# uc2950-v1.net
KiCad netlist of a schematic drawn in EAGLE
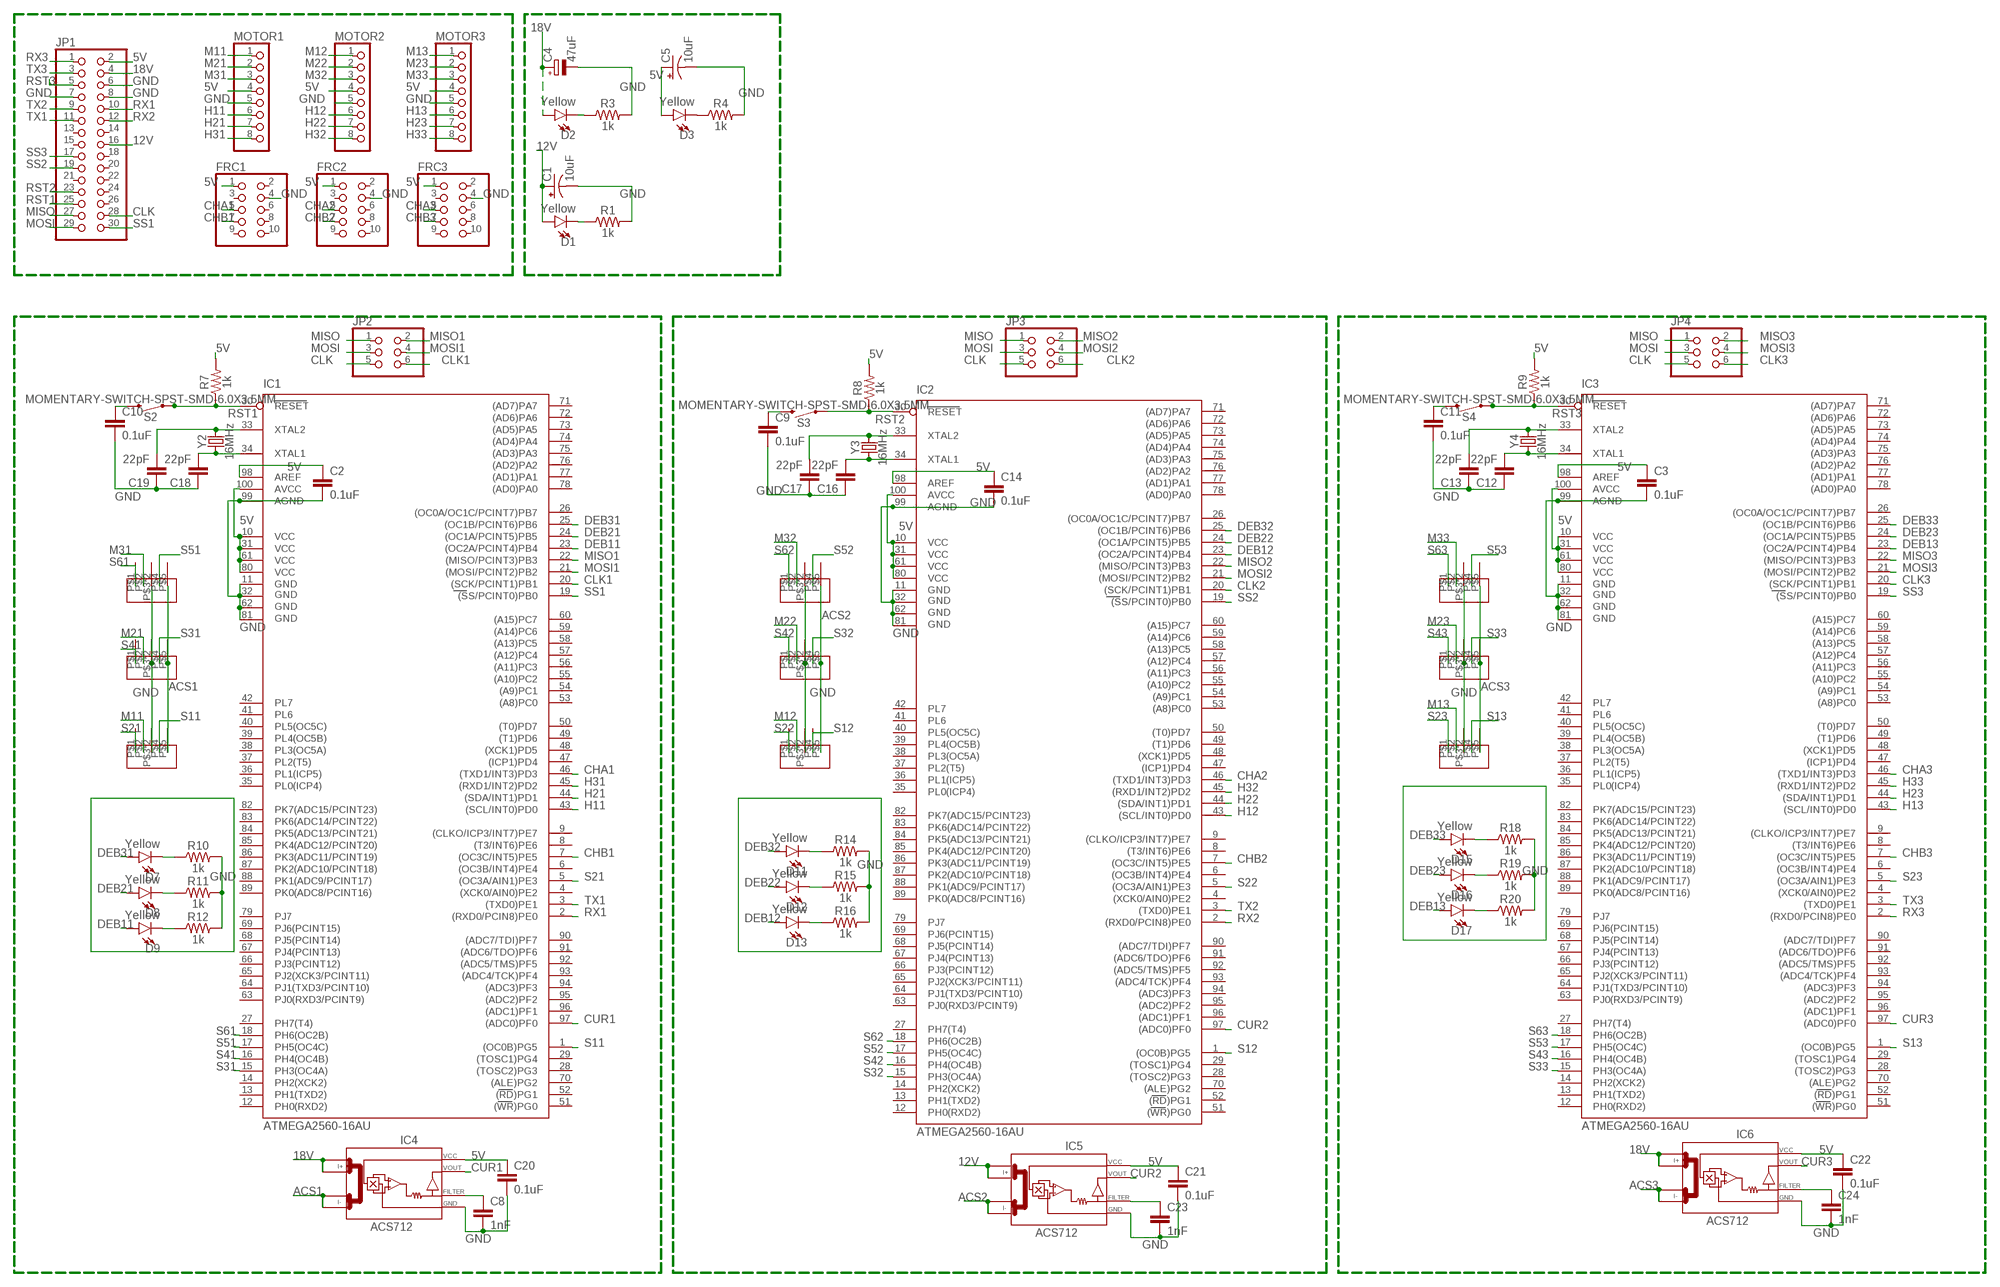
[diagram p0: schematic, sheet 1]

(export (version "E")
  (design (tool "Eeschema 10.0.6"))
  (components
    (comp (ref "C1")
      (value "10uF")
      (footprint "eagle-import:0603-POLAR")
      (libsource (lib "eagle-import") (part "10UF-POLAR-0603-6.3V-20%(TANT)"))
    )
    (comp (ref "C2")
      (value "0.1uF")
      (footprint "eagle-import:0603")
      (libsource (lib "eagle-import") (part "0.1UF-0603-25V-5%"))
    )
    (comp (ref "C3")
      (value "0.1uF")
      (footprint "eagle-import:0603")
      (libsource (lib "eagle-import") (part "0.1UF-0603-25V-5%"))
    )
    (comp (ref "C4")
      (value "47uF")
      (footprint "eagle-import:TAP5-60")
      (libsource (lib "eagle-import") (part "CPOL-EUTAP5-60"))
    )
    (comp (ref "C5")
      (value "10uF")
      (footprint "eagle-import:0603-POLAR")
      (libsource (lib "eagle-import") (part "10UF-POLAR-0603-6.3V-20%(TANT)"))
    )
    (comp (ref "C8")
      (value "1nF")
      (footprint "eagle-import:0603")
      (libsource (lib "eagle-import") (part "1.0NF/1000PF-0603-50V-10%"))
    )
    (comp (ref "C9")
      (value "0.1uF")
      (footprint "eagle-import:0603")
      (libsource (lib "eagle-import") (part "0.1UF-0603-25V-5%"))
    )
    (comp (ref "C10")
      (value "0.1uF")
      (footprint "eagle-import:0603")
      (libsource (lib "eagle-import") (part "0.1UF-0603-25V-5%"))
    )
    (comp (ref "C11")
      (value "0.1uF")
      (footprint "eagle-import:0603")
      (libsource (lib "eagle-import") (part "0.1UF-0603-25V-5%"))
    )
    (comp (ref "C12")
      (value "22pF")
      (footprint "eagle-import:0603")
      (libsource (lib "eagle-import") (part "22PF-0603-50V-5%"))
    )
    (comp (ref "C13")
      (value "22pF")
      (footprint "eagle-import:0603")
      (libsource (lib "eagle-import") (part "22PF-0603-50V-5%"))
    )
    (comp (ref "C14")
      (value "0.1uF")
      (footprint "eagle-import:0603")
      (libsource (lib "eagle-import") (part "0.1UF-0603-25V-5%"))
    )
    (comp (ref "C16")
      (value "22pF")
      (footprint "eagle-import:0603")
      (libsource (lib "eagle-import") (part "22PF-0603-50V-5%"))
    )
    (comp (ref "C17")
      (value "22pF")
      (footprint "eagle-import:0603")
      (libsource (lib "eagle-import") (part "22PF-0603-50V-5%"))
    )
    (comp (ref "C18")
      (value "22pF")
      (footprint "eagle-import:0603")
      (libsource (lib "eagle-import") (part "22PF-0603-50V-5%"))
    )
    (comp (ref "C19")
      (value "22pF")
      (footprint "eagle-import:0603")
      (libsource (lib "eagle-import") (part "22PF-0603-50V-5%"))
    )
    (comp (ref "C20")
      (value "0.1uF")
      (footprint "eagle-import:0603")
      (libsource (lib "eagle-import") (part "0.1UF-0603-25V-5%"))
    )
    (comp (ref "C21")
      (value "0.1uF")
      (footprint "eagle-import:0603")
      (libsource (lib "eagle-import") (part "0.1UF-0603-25V-5%"))
    )
    (comp (ref "C22")
      (value "0.1uF")
      (footprint "eagle-import:0603")
      (libsource (lib "eagle-import") (part "0.1UF-0603-25V-5%"))
    )
    (comp (ref "C23")
      (value "1nF")
      (footprint "eagle-import:0603")
      (libsource (lib "eagle-import") (part "1.0NF/1000PF-0603-50V-10%"))
    )
    (comp (ref "C24")
      (value "1nF")
      (footprint "eagle-import:0603")
      (libsource (lib "eagle-import") (part "1.0NF/1000PF-0603-50V-10%"))
    )
    (comp (ref "D1")
      (value "Yellow")
      (footprint "eagle-import:LED-0603")
      (libsource (lib "eagle-import") (part "LED-YELLOW0603"))
    )
    (comp (ref "D2")
      (value "Yellow")
      (footprint "eagle-import:LED-0603")
      (libsource (lib "eagle-import") (part "LED-YELLOW0603"))
    )
    (comp (ref "D3")
      (value "Yellow")
      (footprint "eagle-import:LED-0603")
      (libsource (lib "eagle-import") (part "LED-YELLOW0603"))
    )
    (comp (ref "D7")
      (value "Yellow")
      (footprint "eagle-import:LED-0603")
      (libsource (lib "eagle-import") (part "LED-YELLOW0603"))
    )
    (comp (ref "D8")
      (value "Yellow")
      (footprint "eagle-import:LED-0603")
      (libsource (lib "eagle-import") (part "LED-YELLOW0603"))
    )
    (comp (ref "D9")
      (value "Yellow")
      (footprint "eagle-import:LED-0603")
      (libsource (lib "eagle-import") (part "LED-YELLOW0603"))
    )
    (comp (ref "D11")
      (value "Yellow")
      (footprint "eagle-import:LED-0603")
      (libsource (lib "eagle-import") (part "LED-YELLOW0603"))
    )
    (comp (ref "D12")
      (value "Yellow")
      (footprint "eagle-import:LED-0603")
      (libsource (lib "eagle-import") (part "LED-YELLOW0603"))
    )
    (comp (ref "D13")
      (value "Yellow")
      (footprint "eagle-import:LED-0603")
      (libsource (lib "eagle-import") (part "LED-YELLOW0603"))
    )
    (comp (ref "D15")
      (value "Yellow")
      (footprint "eagle-import:LED-0603")
      (libsource (lib "eagle-import") (part "LED-YELLOW0603"))
    )
    (comp (ref "D16")
      (value "Yellow")
      (footprint "eagle-import:LED-0603")
      (libsource (lib "eagle-import") (part "LED-YELLOW0603"))
    )
    (comp (ref "D17")
      (value "Yellow")
      (footprint "eagle-import:LED-0603")
      (libsource (lib "eagle-import") (part "LED-YELLOW0603"))
    )
    (comp (ref "FRC1")
      (value "PINHD-2X5")
      (footprint "eagle-import:2X05")
      (libsource (lib "eagle-import") (part "PINHD-2X5"))
    )
    (comp (ref "FRC2")
      (value "PINHD-2X5")
      (footprint "eagle-import:2X05")
      (libsource (lib "eagle-import") (part "PINHD-2X5"))
    )
    (comp (ref "FRC3")
      (value "PINHD-2X5")
      (footprint "eagle-import:2X05")
      (libsource (lib "eagle-import") (part "PINHD-2X5"))
    )
    (comp (ref "IC1")
      (value "ATMEGA2560-16AU")
      (footprint "eagle-import:TQFP100")
      (libsource (lib "eagle-import") (part "ATMEGAAU2560-16"))
    )
    (comp (ref "IC2")
      (value "ATMEGA2560-16AU")
      (footprint "eagle-import:TQFP100")
      (libsource (lib "eagle-import") (part "ATMEGAAU2560-16"))
    )
    (comp (ref "IC3")
      (value "ATMEGA2560-16AU")
      (footprint "eagle-import:TQFP100")
      (libsource (lib "eagle-import") (part "ATMEGAAU2560-16"))
    )
    (comp (ref "IC4")
      (value "ACS712")
      (footprint "eagle-import:SO08")
      (libsource (lib "eagle-import") (part "ACS712"))
    )
    (comp (ref "IC5")
      (value "ACS712")
      (footprint "eagle-import:SO08")
      (libsource (lib "eagle-import") (part "ACS712"))
    )
    (comp (ref "IC6")
      (value "ACS712")
      (footprint "eagle-import:SO08")
      (libsource (lib "eagle-import") (part "ACS712"))
    )
    (comp (ref "JP1")
      (value "PINHD-2X15/90")
      (footprint "eagle-import:2X15_90")
      (libsource (lib "eagle-import") (part "PINHD-2X15/90"))
    )
    (comp (ref "JP2")
      (value "PINHD-2X3")
      (footprint "eagle-import:2X03")
      (libsource (lib "eagle-import") (part "PINHD-2X3"))
    )
    (comp (ref "JP3")
      (value "PINHD-2X3")
      (footprint "eagle-import:2X03")
      (libsource (lib "eagle-import") (part "PINHD-2X3"))
    )
    (comp (ref "JP4")
      (value "PINHD-2X3")
      (footprint "eagle-import:2X03")
      (libsource (lib "eagle-import") (part "PINHD-2X3"))
    )
    (comp (ref "MIC1")
      (value "UC2950")
      (footprint "eagle-import:UC2950")
      (libsource (lib "eagle-import") (part "UC2950"))
    )
    (comp (ref "MIC2")
      (value "UC2950")
      (footprint "eagle-import:UC2950")
      (libsource (lib "eagle-import") (part "UC2950"))
    )
    (comp (ref "MIC3")
      (value "UC2950")
      (footprint "eagle-import:UC2950")
      (libsource (lib "eagle-import") (part "UC2950"))
    )
    (comp (ref "MIC4")
      (value "UC2950")
      (footprint "eagle-import:UC2950")
      (libsource (lib "eagle-import") (part "UC2950"))
    )
    (comp (ref "MIC5")
      (value "UC2950")
      (footprint "eagle-import:UC2950")
      (libsource (lib "eagle-import") (part "UC2950"))
    )
    (comp (ref "MIC6")
      (value "UC2950")
      (footprint "eagle-import:UC2950")
      (libsource (lib "eagle-import") (part "UC2950"))
    )
    (comp (ref "MIC7")
      (value "UC2950")
      (footprint "eagle-import:UC2950")
      (libsource (lib "eagle-import") (part "UC2950"))
    )
    (comp (ref "MIC8")
      (value "UC2950")
      (footprint "eagle-import:UC2950")
      (libsource (lib "eagle-import") (part "UC2950"))
    )
    (comp (ref "MIC9")
      (value "UC2950")
      (footprint "eagle-import:UC2950")
      (libsource (lib "eagle-import") (part "UC2950"))
    )
    (comp (ref "MOTOR1")
      (value "PINHD-1X8")
      (footprint "eagle-import:1X08")
      (libsource (lib "eagle-import") (part "PINHD-1X8"))
    )
    (comp (ref "MOTOR2")
      (value "PINHD-1X8")
      (footprint "eagle-import:1X08")
      (libsource (lib "eagle-import") (part "PINHD-1X8"))
    )
    (comp (ref "MOTOR3")
      (value "PINHD-1X8")
      (footprint "eagle-import:1X08")
      (libsource (lib "eagle-import") (part "PINHD-1X8"))
    )
    (comp (ref "R1")
      (value "1k")
      (footprint "eagle-import:0603")
      (libsource (lib "eagle-import") (part "1KOHM-0603-1/10W-1%"))
    )
    (comp (ref "R3")
      (value "1k")
      (footprint "eagle-import:0603")
      (libsource (lib "eagle-import") (part "1KOHM-0603-1/10W-1%"))
    )
    (comp (ref "R4")
      (value "1k")
      (footprint "eagle-import:0603")
      (libsource (lib "eagle-import") (part "1KOHM-0603-1/10W-1%"))
    )
    (comp (ref "R7")
      (value "1k")
      (footprint "eagle-import:0603")
      (libsource (lib "eagle-import") (part "1KOHM-0603-1/10W-1%"))
    )
    (comp (ref "R8")
      (value "1k")
      (footprint "eagle-import:0603")
      (libsource (lib "eagle-import") (part "1KOHM-0603-1/10W-1%"))
    )
    (comp (ref "R9")
      (value "1k")
      (footprint "eagle-import:0603")
      (libsource (lib "eagle-import") (part "1KOHM-0603-1/10W-1%"))
    )
    (comp (ref "R10")
      (value "1k")
      (footprint "eagle-import:0603")
      (libsource (lib "eagle-import") (part "1KOHM-0603-1/10W-1%"))
    )
    (comp (ref "R11")
      (value "1k")
      (footprint "eagle-import:0603")
      (libsource (lib "eagle-import") (part "1KOHM-0603-1/10W-1%"))
    )
    (comp (ref "R12")
      (value "1k")
      (footprint "eagle-import:0603")
      (libsource (lib "eagle-import") (part "1KOHM-0603-1/10W-1%"))
    )
    (comp (ref "R14")
      (value "1k")
      (footprint "eagle-import:0603")
      (libsource (lib "eagle-import") (part "1KOHM-0603-1/10W-1%"))
    )
    (comp (ref "R15")
      (value "1k")
      (footprint "eagle-import:0603")
      (libsource (lib "eagle-import") (part "1KOHM-0603-1/10W-1%"))
    )
    (comp (ref "R16")
      (value "1k")
      (footprint "eagle-import:0603")
      (libsource (lib "eagle-import") (part "1KOHM-0603-1/10W-1%"))
    )
    (comp (ref "R18")
      (value "1k")
      (footprint "eagle-import:0603")
      (libsource (lib "eagle-import") (part "1KOHM-0603-1/10W-1%"))
    )
    (comp (ref "R19")
      (value "1k")
      (footprint "eagle-import:0603")
      (libsource (lib "eagle-import") (part "1KOHM-0603-1/10W-1%"))
    )
    (comp (ref "R20")
      (value "1k")
      (footprint "eagle-import:0603")
      (libsource (lib "eagle-import") (part "1KOHM-0603-1/10W-1%"))
    )
    (comp (ref "S2")
      (value "MOMENTARY-SWITCH-SPST-SMD-6.0X3.5MM")
      (footprint "eagle-import:TACTILE_SWITCH_SMD_6.0X3.5MM")
      (libsource (lib "eagle-import") (part "MOMENTARY-SWITCH-SPST-SMD-6.0X3.5MM"))
    )
    (comp (ref "S3")
      (value "MOMENTARY-SWITCH-SPST-SMD-6.0X3.5MM")
      (footprint "eagle-import:TACTILE_SWITCH_SMD_6.0X3.5MM")
      (libsource (lib "eagle-import") (part "MOMENTARY-SWITCH-SPST-SMD-6.0X3.5MM"))
    )
    (comp (ref "S4")
      (value "MOMENTARY-SWITCH-SPST-SMD-6.0X3.5MM")
      (footprint "eagle-import:TACTILE_SWITCH_SMD_6.0X3.5MM")
      (libsource (lib "eagle-import") (part "MOMENTARY-SWITCH-SPST-SMD-6.0X3.5MM"))
    )
    (comp (ref "Y2")
      (value "16MHz")
      (footprint "eagle-import:CRYSTAL-SMD-5X3.2-4PAD")
      (libsource (lib "eagle-import") (part "CRYSTAL-16MHZSMD-5X3.2"))
    )
    (comp (ref "Y3")
      (value "16MHz")
      (footprint "eagle-import:CRYSTAL-SMD-5X3.2-4PAD")
      (libsource (lib "eagle-import") (part "CRYSTAL-16MHZSMD-5X3.2"))
    )
    (comp (ref "Y4")
      (value "16MHz")
      (footprint "eagle-import:CRYSTAL-SMD-5X3.2-4PAD")
      (libsource (lib "eagle-import") (part "CRYSTAL-16MHZSMD-5X3.2"))
    )
  )
  (nets
    (net (code "1") (name "/5V") (class "Default")
      (node (ref "C14") (pin "1") (pinfunction "1_1") (pintype "passive"))
      (node (ref "C2") (pin "1") (pinfunction "1_1") (pintype "passive"))
      (node (ref "C20") (pin "1") (pinfunction "1_1") (pintype "passive"))
      (node (ref "C21") (pin "1") (pinfunction "1_1") (pintype "passive"))
      (node (ref "C22") (pin "1") (pinfunction "1_1") (pintype "passive"))
      (node (ref "C3") (pin "1") (pinfunction "1_1") (pintype "passive"))
      (node (ref "C5") (pin "+") (pinfunction "+_+") (pintype "passive"))
      (node (ref "D3") (pin "A") (pinfunction "A_A") (pintype "passive"))
      (node (ref "FRC1") (pin "1") (pinfunction "1_1") (pintype "passive"))
      (node (ref "FRC2") (pin "1") (pinfunction "1_1") (pintype "passive"))
      (node (ref "FRC3") (pin "1") (pinfunction "1_1") (pintype "passive"))
      (node (ref "IC1") (pin "10") (pinfunction "VCC_10") (pintype "power_in"))
      (node (ref "IC1") (pin "100") (pinfunction "AVCC_100") (pintype "power_in"))
      (node (ref "IC1") (pin "31") (pinfunction "VCC1_31") (pintype "power_in"))
      (node (ref "IC1") (pin "61") (pinfunction "VCC2_61") (pintype "power_in"))
      (node (ref "IC1") (pin "80") (pinfunction "VCC3_80") (pintype "power_in"))
      (node (ref "IC1") (pin "98") (pinfunction "AREF_98") (pintype "bidirectional"))
      (node (ref "IC2") (pin "10") (pinfunction "VCC_10") (pintype "power_in"))
      (node (ref "IC2") (pin "100") (pinfunction "AVCC_100") (pintype "power_in"))
      (node (ref "IC2") (pin "31") (pinfunction "VCC1_31") (pintype "power_in"))
      (node (ref "IC2") (pin "61") (pinfunction "VCC2_61") (pintype "power_in"))
      (node (ref "IC2") (pin "80") (pinfunction "VCC3_80") (pintype "power_in"))
      (node (ref "IC2") (pin "98") (pinfunction "AREF_98") (pintype "bidirectional"))
      (node (ref "IC3") (pin "10") (pinfunction "VCC_10") (pintype "power_in"))
      (node (ref "IC3") (pin "100") (pinfunction "AVCC_100") (pintype "power_in"))
      (node (ref "IC3") (pin "31") (pinfunction "VCC1_31") (pintype "power_in"))
      (node (ref "IC3") (pin "61") (pinfunction "VCC2_61") (pintype "power_in"))
      (node (ref "IC3") (pin "80") (pinfunction "VCC3_80") (pintype "power_in"))
      (node (ref "IC3") (pin "98") (pinfunction "AREF_98") (pintype "bidirectional"))
      (node (ref "IC4") (pin "8") (pinfunction "VCC_8") (pintype "power_in"))
      (node (ref "IC5") (pin "8") (pinfunction "VCC_8") (pintype "power_in"))
      (node (ref "IC6") (pin "8") (pinfunction "VCC_8") (pintype "power_in"))
      (node (ref "JP1") (pin "2") (pinfunction "2_2") (pintype "passive"))
      (node (ref "MOTOR1") (pin "4") (pinfunction "4_4") (pintype "passive"))
      (node (ref "MOTOR2") (pin "4") (pinfunction "4_4") (pintype "passive"))
      (node (ref "MOTOR3") (pin "4") (pinfunction "4_4") (pintype "passive"))
      (node (ref "R7") (pin "2") (pinfunction "2_2") (pintype "passive"))
      (node (ref "R8") (pin "2") (pinfunction "2_2") (pintype "passive"))
      (node (ref "R9") (pin "2") (pinfunction "2_2") (pintype "passive"))
    )
    (net (code "2") (name "/12V") (class "Default")
      (node (ref "C1") (pin "+") (pinfunction "+_+") (pintype "passive"))
      (node (ref "D1") (pin "A") (pinfunction "A_A") (pintype "passive"))
      (node (ref "IC5") (pin "1") (pinfunction "I+_0_1") (pintype "bidirectional"))
      (node (ref "IC5") (pin "2") (pinfunction "I+_1_2") (pintype "bidirectional"))
      (node (ref "JP1") (pin "16") (pinfunction "16_16") (pintype "passive"))
    )
    (net (code "3") (name "/18V") (class "Default")
      (node (ref "C4") (pin "+") (pinfunction "+_+") (pintype "passive"))
      (node (ref "D2") (pin "A") (pinfunction "A_A") (pintype "passive"))
      (node (ref "IC4") (pin "1") (pinfunction "I+_0_1") (pintype "bidirectional"))
      (node (ref "IC4") (pin "2") (pinfunction "I+_1_2") (pintype "bidirectional"))
      (node (ref "IC6") (pin "1") (pinfunction "I+_0_1") (pintype "bidirectional"))
      (node (ref "IC6") (pin "2") (pinfunction "I+_1_2") (pintype "bidirectional"))
      (node (ref "JP1") (pin "4") (pinfunction "4_4") (pintype "passive"))
    )
    (net (code "4") (name "/ACS1") (class "Default")
      (node (ref "IC4") (pin "3") (pinfunction "I-_0_3") (pintype "bidirectional"))
      (node (ref "IC4") (pin "4") (pinfunction "I-_1_4") (pintype "bidirectional"))
      (node (ref "MIC1") (pin "P$5") (pinfunction "P$5_P$5") (pintype "bidirectional"))
      (node (ref "MIC2") (pin "P$5") (pinfunction "P$5_P$5") (pintype "bidirectional"))
      (node (ref "MIC3") (pin "P$5") (pinfunction "P$5_P$5") (pintype "bidirectional"))
    )
    (net (code "5") (name "/ACS2") (class "Default")
      (node (ref "IC5") (pin "3") (pinfunction "I-_0_3") (pintype "bidirectional"))
      (node (ref "IC5") (pin "4") (pinfunction "I-_1_4") (pintype "bidirectional"))
      (node (ref "MIC4") (pin "P$5") (pinfunction "P$5_P$5") (pintype "bidirectional"))
      (node (ref "MIC5") (pin "P$5") (pinfunction "P$5_P$5") (pintype "bidirectional"))
      (node (ref "MIC6") (pin "P$5") (pinfunction "P$5_P$5") (pintype "bidirectional"))
    )
    (net (code "6") (name "/ACS3") (class "Default")
      (node (ref "IC6") (pin "3") (pinfunction "I-_0_3") (pintype "bidirectional"))
      (node (ref "IC6") (pin "4") (pinfunction "I-_1_4") (pintype "bidirectional"))
      (node (ref "MIC7") (pin "P$5") (pinfunction "P$5_P$5") (pintype "bidirectional"))
      (node (ref "MIC8") (pin "P$5") (pinfunction "P$5_P$5") (pintype "bidirectional"))
      (node (ref "MIC9") (pin "P$5") (pinfunction "P$5_P$5") (pintype "bidirectional"))
    )
    (net (code "7") (name "/CHA1") (class "Default")
      (node (ref "FRC1") (pin "5") (pinfunction "5_5") (pintype "passive"))
      (node (ref "IC1") (pin "46") (pinfunction "(TXD1/INT3)PD3_46") (pintype "bidirectional"))
    )
    (net (code "8") (name "/CHA2") (class "Default")
      (node (ref "FRC2") (pin "5") (pinfunction "5_5") (pintype "passive"))
      (node (ref "IC2") (pin "46") (pinfunction "(TXD1/INT3)PD3_46") (pintype "bidirectional"))
    )
    (net (code "9") (name "/CHA3") (class "Default")
      (node (ref "FRC3") (pin "5") (pinfunction "5_5") (pintype "passive"))
      (node (ref "IC3") (pin "46") (pinfunction "(TXD1/INT3)PD3_46") (pintype "bidirectional"))
    )
    (net (code "10") (name "/CHB1") (class "Default")
      (node (ref "FRC1") (pin "7") (pinfunction "7_7") (pintype "passive"))
      (node (ref "IC1") (pin "7") (pinfunction "(OC3C/INT5)PE5_7") (pintype "bidirectional"))
    )
    (net (code "11") (name "/CHB2") (class "Default")
      (node (ref "FRC2") (pin "7") (pinfunction "7_7") (pintype "passive"))
      (node (ref "IC2") (pin "7") (pinfunction "(OC3C/INT5)PE5_7") (pintype "bidirectional"))
    )
    (net (code "12") (name "/CHB3") (class "Default")
      (node (ref "FRC3") (pin "7") (pinfunction "7_7") (pintype "passive"))
      (node (ref "IC3") (pin "7") (pinfunction "(OC3C/INT5)PE5_7") (pintype "bidirectional"))
    )
    (net (code "13") (name "/CLK") (class "Default")
      (node (ref "JP1") (pin "28") (pinfunction "28_28") (pintype "passive"))
      (node (ref "JP2") (pin "5") (pinfunction "5_5") (pintype "passive"))
      (node (ref "JP3") (pin "5") (pinfunction "5_5") (pintype "passive"))
      (node (ref "JP4") (pin "5") (pinfunction "5_5") (pintype "passive"))
    )
    (net (code "14") (name "/CLK1") (class "Default")
      (node (ref "IC1") (pin "20") (pinfunction "(SCK/PCINT1)PB1_20") (pintype "bidirectional"))
      (node (ref "JP2") (pin "6") (pinfunction "6_6") (pintype "passive"))
    )
    (net (code "15") (name "/CLK2") (class "Default")
      (node (ref "IC2") (pin "20") (pinfunction "(SCK/PCINT1)PB1_20") (pintype "bidirectional"))
      (node (ref "JP3") (pin "6") (pinfunction "6_6") (pintype "passive"))
    )
    (net (code "16") (name "/CLK3") (class "Default")
      (node (ref "IC3") (pin "20") (pinfunction "(SCK/PCINT1)PB1_20") (pintype "bidirectional"))
      (node (ref "JP4") (pin "6") (pinfunction "6_6") (pintype "passive"))
    )
    (net (code "17") (name "/CUR1") (class "Default")
      (node (ref "IC1") (pin "97") (pinfunction "(ADC0)PF0_97") (pintype "bidirectional"))
      (node (ref "IC4") (pin "7") (pinfunction "VOUT_7") (pintype "output"))
    )
    (net (code "18") (name "/CUR2") (class "Default")
      (node (ref "IC2") (pin "97") (pinfunction "(ADC0)PF0_97") (pintype "bidirectional"))
      (node (ref "IC5") (pin "7") (pinfunction "VOUT_7") (pintype "output"))
    )
    (net (code "19") (name "/CUR3") (class "Default")
      (node (ref "IC3") (pin "97") (pinfunction "(ADC0)PF0_97") (pintype "bidirectional"))
      (node (ref "IC6") (pin "7") (pinfunction "VOUT_7") (pintype "output"))
    )
    (net (code "20") (name "/DEB11") (class "Default")
      (node (ref "D9") (pin "A") (pinfunction "A_A") (pintype "passive"))
      (node (ref "IC1") (pin "23") (pinfunction "(OC2A/PCINT4)PB4_23") (pintype "bidirectional"))
    )
    (net (code "21") (name "/DEB12") (class "Default")
      (node (ref "D13") (pin "A") (pinfunction "A_A") (pintype "passive"))
      (node (ref "IC2") (pin "23") (pinfunction "(OC2A/PCINT4)PB4_23") (pintype "bidirectional"))
    )
    (net (code "22") (name "/DEB13") (class "Default")
      (node (ref "D17") (pin "A") (pinfunction "A_A") (pintype "passive"))
      (node (ref "IC3") (pin "23") (pinfunction "(OC2A/PCINT4)PB4_23") (pintype "bidirectional"))
    )
    (net (code "23") (name "/DEB21") (class "Default")
      (node (ref "D8") (pin "A") (pinfunction "A_A") (pintype "passive"))
      (node (ref "IC1") (pin "24") (pinfunction "(OC1A/PCINT5)PB5_24") (pintype "bidirectional"))
    )
    (net (code "24") (name "/DEB22") (class "Default")
      (node (ref "D12") (pin "A") (pinfunction "A_A") (pintype "passive"))
      (node (ref "IC2") (pin "24") (pinfunction "(OC1A/PCINT5)PB5_24") (pintype "bidirectional"))
    )
    (net (code "25") (name "/DEB23") (class "Default")
      (node (ref "D16") (pin "A") (pinfunction "A_A") (pintype "passive"))
      (node (ref "IC3") (pin "24") (pinfunction "(OC1A/PCINT5)PB5_24") (pintype "bidirectional"))
    )
    (net (code "26") (name "/DEB31") (class "Default")
      (node (ref "D7") (pin "A") (pinfunction "A_A") (pintype "passive"))
      (node (ref "IC1") (pin "25") (pinfunction "(OC1B/PCINT6)PB6_25") (pintype "bidirectional"))
    )
    (net (code "27") (name "/DEB32") (class "Default")
      (node (ref "D11") (pin "A") (pinfunction "A_A") (pintype "passive"))
      (node (ref "IC2") (pin "25") (pinfunction "(OC1B/PCINT6)PB6_25") (pintype "bidirectional"))
    )
    (net (code "28") (name "/DEB33") (class "Default")
      (node (ref "D15") (pin "A") (pinfunction "A_A") (pintype "passive"))
      (node (ref "IC3") (pin "25") (pinfunction "(OC1B/PCINT6)PB6_25") (pintype "bidirectional"))
    )
    (net (code "29") (name "/GND") (class "Default")
      (node (ref "C1") (pin "-") (pinfunction "-_-") (pintype "passive"))
      (node (ref "C10") (pin "2") (pinfunction "2_2") (pintype "passive"))
      (node (ref "C11") (pin "2") (pinfunction "2_2") (pintype "passive"))
      (node (ref "C12") (pin "1") (pinfunction "1_1") (pintype "passive"))
      (node (ref "C13") (pin "1") (pinfunction "1_1") (pintype "passive"))
      (node (ref "C14") (pin "2") (pinfunction "2_2") (pintype "passive"))
      (node (ref "C16") (pin "1") (pinfunction "1_1") (pintype "passive"))
      (node (ref "C17") (pin "1") (pinfunction "1_1") (pintype "passive"))
      (node (ref "C18") (pin "1") (pinfunction "1_1") (pintype "passive"))
      (node (ref "C19") (pin "1") (pinfunction "1_1") (pintype "passive"))
      (node (ref "C2") (pin "2") (pinfunction "2_2") (pintype "passive"))
      (node (ref "C20") (pin "2") (pinfunction "2_2") (pintype "passive"))
      (node (ref "C21") (pin "2") (pinfunction "2_2") (pintype "passive"))
      (node (ref "C22") (pin "2") (pinfunction "2_2") (pintype "passive"))
      (node (ref "C23") (pin "2") (pinfunction "2_2") (pintype "passive"))
      (node (ref "C24") (pin "2") (pinfunction "2_2") (pintype "passive"))
      (node (ref "C3") (pin "2") (pinfunction "2_2") (pintype "passive"))
      (node (ref "C4") (pin "-") (pinfunction "-_-") (pintype "passive"))
      (node (ref "C5") (pin "-") (pinfunction "-_-") (pintype "passive"))
      (node (ref "C8") (pin "2") (pinfunction "2_2") (pintype "passive"))
      (node (ref "C9") (pin "2") (pinfunction "2_2") (pintype "passive"))
      (node (ref "FRC1") (pin "4") (pinfunction "4_4") (pintype "passive"))
      (node (ref "FRC2") (pin "4") (pinfunction "4_4") (pintype "passive"))
      (node (ref "FRC3") (pin "4") (pinfunction "4_4") (pintype "passive"))
      (node (ref "IC1") (pin "11") (pinfunction "GND_11") (pintype "power_in"))
      (node (ref "IC1") (pin "32") (pinfunction "GND1_32") (pintype "power_in"))
      (node (ref "IC1") (pin "62") (pinfunction "GND2_62") (pintype "power_in"))
      (node (ref "IC1") (pin "81") (pinfunction "GND3_81") (pintype "power_in"))
      (node (ref "IC1") (pin "99") (pinfunction "AGND_99") (pintype "power_in"))
      (node (ref "IC2") (pin "11") (pinfunction "GND_11") (pintype "power_in"))
      (node (ref "IC2") (pin "32") (pinfunction "GND1_32") (pintype "power_in"))
      (node (ref "IC2") (pin "62") (pinfunction "GND2_62") (pintype "power_in"))
      (node (ref "IC2") (pin "81") (pinfunction "GND3_81") (pintype "power_in"))
      (node (ref "IC2") (pin "99") (pinfunction "AGND_99") (pintype "power_in"))
      (node (ref "IC3") (pin "11") (pinfunction "GND_11") (pintype "power_in"))
      (node (ref "IC3") (pin "32") (pinfunction "GND1_32") (pintype "power_in"))
      (node (ref "IC3") (pin "62") (pinfunction "GND2_62") (pintype "power_in"))
      (node (ref "IC3") (pin "81") (pinfunction "GND3_81") (pintype "power_in"))
      (node (ref "IC3") (pin "99") (pinfunction "AGND_99") (pintype "power_in"))
      (node (ref "IC4") (pin "5") (pinfunction "GND_5") (pintype "power_in"))
      (node (ref "IC5") (pin "5") (pinfunction "GND_5") (pintype "power_in"))
      (node (ref "IC6") (pin "5") (pinfunction "GND_5") (pintype "power_in"))
      (node (ref "JP1") (pin "6") (pinfunction "6_6") (pintype "passive"))
      (node (ref "JP1") (pin "7") (pinfunction "7_7") (pintype "passive"))
      (node (ref "JP1") (pin "8") (pinfunction "8_8") (pintype "passive"))
      (node (ref "MIC1") (pin "P$3") (pinfunction "P$3_P$3") (pintype "bidirectional"))
      (node (ref "MIC1") (pin "P$6") (pinfunction "P$3_P$6") (pintype "bidirectional"))
      (node (ref "MIC2") (pin "P$3") (pinfunction "P$3_P$3") (pintype "bidirectional"))
      (node (ref "MIC2") (pin "P$6") (pinfunction "P$3_P$6") (pintype "bidirectional"))
      (node (ref "MIC3") (pin "P$3") (pinfunction "P$3_P$3") (pintype "bidirectional"))
      (node (ref "MIC3") (pin "P$6") (pinfunction "P$3_P$6") (pintype "bidirectional"))
      (node (ref "MIC4") (pin "P$3") (pinfunction "P$3_P$3") (pintype "bidirectional"))
      (node (ref "MIC4") (pin "P$6") (pinfunction "P$3_P$6") (pintype "bidirectional"))
      (node (ref "MIC5") (pin "P$3") (pinfunction "P$3_P$3") (pintype "bidirectional"))
      (node (ref "MIC5") (pin "P$6") (pinfunction "P$3_P$6") (pintype "bidirectional"))
      (node (ref "MIC6") (pin "P$3") (pinfunction "P$3_P$3") (pintype "bidirectional"))
      (node (ref "MIC6") (pin "P$6") (pinfunction "P$3_P$6") (pintype "bidirectional"))
      (node (ref "MIC7") (pin "P$3") (pinfunction "P$3_P$3") (pintype "bidirectional"))
      (node (ref "MIC7") (pin "P$6") (pinfunction "P$3_P$6") (pintype "bidirectional"))
      (node (ref "MIC8") (pin "P$3") (pinfunction "P$3_P$3") (pintype "bidirectional"))
      (node (ref "MIC8") (pin "P$6") (pinfunction "P$3_P$6") (pintype "bidirectional"))
      (node (ref "MIC9") (pin "P$3") (pinfunction "P$3_P$3") (pintype "bidirectional"))
      (node (ref "MIC9") (pin "P$6") (pinfunction "P$3_P$6") (pintype "bidirectional"))
      (node (ref "MOTOR1") (pin "5") (pinfunction "5_5") (pintype "passive"))
      (node (ref "MOTOR2") (pin "5") (pinfunction "5_5") (pintype "passive"))
      (node (ref "MOTOR3") (pin "5") (pinfunction "5_5") (pintype "passive"))
      (node (ref "R1") (pin "2") (pinfunction "2_2") (pintype "passive"))
      (node (ref "R10") (pin "2") (pinfunction "2_2") (pintype "passive"))
      (node (ref "R11") (pin "2") (pinfunction "2_2") (pintype "passive"))
      (node (ref "R12") (pin "2") (pinfunction "2_2") (pintype "passive"))
      (node (ref "R14") (pin "2") (pinfunction "2_2") (pintype "passive"))
      (node (ref "R15") (pin "2") (pinfunction "2_2") (pintype "passive"))
      (node (ref "R16") (pin "2") (pinfunction "2_2") (pintype "passive"))
      (node (ref "R18") (pin "2") (pinfunction "2_2") (pintype "passive"))
      (node (ref "R19") (pin "2") (pinfunction "2_2") (pintype "passive"))
      (node (ref "R20") (pin "2") (pinfunction "2_2") (pintype "passive"))
      (node (ref "R3") (pin "2") (pinfunction "2_2") (pintype "passive"))
      (node (ref "R4") (pin "2") (pinfunction "2_2") (pintype "passive"))
    )
    (net (code "30") (name "/H11") (class "Default")
      (node (ref "IC1") (pin "43") (pinfunction "(SCL/INT0)PD0_43") (pintype "bidirectional"))
      (node (ref "MOTOR1") (pin "6") (pinfunction "6_6") (pintype "passive"))
    )
    (net (code "31") (name "/H12") (class "Default")
      (node (ref "IC2") (pin "43") (pinfunction "(SCL/INT0)PD0_43") (pintype "bidirectional"))
      (node (ref "MOTOR2") (pin "6") (pinfunction "6_6") (pintype "passive"))
    )
    (net (code "32") (name "/H13") (class "Default")
      (node (ref "IC3") (pin "43") (pinfunction "(SCL/INT0)PD0_43") (pintype "bidirectional"))
      (node (ref "MOTOR3") (pin "6") (pinfunction "6_6") (pintype "passive"))
    )
    (net (code "33") (name "/H21") (class "Default")
      (node (ref "IC1") (pin "44") (pinfunction "(SDA/INT1)PD1_44") (pintype "bidirectional"))
      (node (ref "MOTOR1") (pin "7") (pinfunction "7_7") (pintype "passive"))
    )
    (net (code "34") (name "/H22") (class "Default")
      (node (ref "IC2") (pin "44") (pinfunction "(SDA/INT1)PD1_44") (pintype "bidirectional"))
      (node (ref "MOTOR2") (pin "7") (pinfunction "7_7") (pintype "passive"))
    )
    (net (code "35") (name "/H23") (class "Default")
      (node (ref "IC3") (pin "44") (pinfunction "(SDA/INT1)PD1_44") (pintype "bidirectional"))
      (node (ref "MOTOR3") (pin "7") (pinfunction "7_7") (pintype "passive"))
    )
    (net (code "36") (name "/H31") (class "Default")
      (node (ref "IC1") (pin "45") (pinfunction "(RXD1/INT2)PD2_45") (pintype "bidirectional"))
      (node (ref "MOTOR1") (pin "8") (pinfunction "8_8") (pintype "passive"))
    )
    (net (code "37") (name "/H32") (class "Default")
      (node (ref "IC2") (pin "45") (pinfunction "(RXD1/INT2)PD2_45") (pintype "bidirectional"))
      (node (ref "MOTOR2") (pin "8") (pinfunction "8_8") (pintype "passive"))
    )
    (net (code "38") (name "/H33") (class "Default")
      (node (ref "IC3") (pin "45") (pinfunction "(RXD1/INT2)PD2_45") (pintype "bidirectional"))
      (node (ref "MOTOR3") (pin "8") (pinfunction "8_8") (pintype "passive"))
    )
    (net (code "39") (name "/M11") (class "Default")
      (node (ref "MIC3") (pin "P$2") (pinfunction "P$2_P$2") (pintype "bidirectional"))
      (node (ref "MOTOR1") (pin "1") (pinfunction "1_1") (pintype "passive"))
    )
    (net (code "40") (name "/M12") (class "Default")
      (node (ref "MIC6") (pin "P$2") (pinfunction "P$2_P$2") (pintype "bidirectional"))
      (node (ref "MOTOR2") (pin "1") (pinfunction "1_1") (pintype "passive"))
    )
    (net (code "41") (name "/M13") (class "Default")
      (node (ref "MIC7") (pin "P$2") (pinfunction "P$2_P$2") (pintype "bidirectional"))
      (node (ref "MOTOR3") (pin "1") (pinfunction "1_1") (pintype "passive"))
    )
    (net (code "42") (name "/M21") (class "Default")
      (node (ref "MIC2") (pin "P$2") (pinfunction "P$2_P$2") (pintype "bidirectional"))
      (node (ref "MOTOR1") (pin "2") (pinfunction "2_2") (pintype "passive"))
    )
    (net (code "43") (name "/M22") (class "Default")
      (node (ref "MIC5") (pin "P$2") (pinfunction "P$2_P$2") (pintype "bidirectional"))
      (node (ref "MOTOR2") (pin "2") (pinfunction "2_2") (pintype "passive"))
    )
    (net (code "44") (name "/M23") (class "Default")
      (node (ref "MIC8") (pin "P$2") (pinfunction "P$2_P$2") (pintype "bidirectional"))
      (node (ref "MOTOR3") (pin "2") (pinfunction "2_2") (pintype "passive"))
    )
    (net (code "45") (name "/M31") (class "Default")
      (node (ref "MIC1") (pin "P$2") (pinfunction "P$2_P$2") (pintype "bidirectional"))
      (node (ref "MOTOR1") (pin "3") (pinfunction "3_3") (pintype "passive"))
    )
    (net (code "46") (name "/M32") (class "Default")
      (node (ref "MIC4") (pin "P$2") (pinfunction "P$2_P$2") (pintype "bidirectional"))
      (node (ref "MOTOR2") (pin "3") (pinfunction "3_3") (pintype "passive"))
    )
    (net (code "47") (name "/M33") (class "Default")
      (node (ref "MIC9") (pin "P$2") (pinfunction "P$2_P$2") (pintype "bidirectional"))
      (node (ref "MOTOR3") (pin "3") (pinfunction "3_3") (pintype "passive"))
    )
    (net (code "48") (name "/MISO") (class "Default")
      (node (ref "JP1") (pin "27") (pinfunction "27_27") (pintype "passive"))
      (node (ref "JP2") (pin "1") (pinfunction "1_1") (pintype "passive"))
      (node (ref "JP3") (pin "1") (pinfunction "1_1") (pintype "passive"))
      (node (ref "JP4") (pin "1") (pinfunction "1_1") (pintype "passive"))
    )
    (net (code "49") (name "/MISO1") (class "Default")
      (node (ref "IC1") (pin "22") (pinfunction "(MISO/PCINT3)PB3_22") (pintype "bidirectional"))
      (node (ref "JP2") (pin "2") (pinfunction "2_2") (pintype "passive"))
    )
    (net (code "50") (name "/MISO2") (class "Default")
      (node (ref "IC2") (pin "22") (pinfunction "(MISO/PCINT3)PB3_22") (pintype "bidirectional"))
      (node (ref "JP3") (pin "2") (pinfunction "2_2") (pintype "passive"))
    )
    (net (code "51") (name "/MISO3") (class "Default")
      (node (ref "IC3") (pin "22") (pinfunction "(MISO/PCINT3)PB3_22") (pintype "bidirectional"))
      (node (ref "JP4") (pin "2") (pinfunction "2_2") (pintype "passive"))
    )
    (net (code "52") (name "/MOSI") (class "Default")
      (node (ref "JP1") (pin "29") (pinfunction "29_29") (pintype "passive"))
      (node (ref "JP2") (pin "3") (pinfunction "3_3") (pintype "passive"))
      (node (ref "JP3") (pin "3") (pinfunction "3_3") (pintype "passive"))
      (node (ref "JP4") (pin "3") (pinfunction "3_3") (pintype "passive"))
    )
    (net (code "53") (name "/MOSI1") (class "Default")
      (node (ref "IC1") (pin "21") (pinfunction "(MOSI/PCINT2)PB2_21") (pintype "bidirectional"))
      (node (ref "JP2") (pin "4") (pinfunction "4_4") (pintype "passive"))
    )
    (net (code "54") (name "/MOSI2") (class "Default")
      (node (ref "IC2") (pin "21") (pinfunction "(MOSI/PCINT2)PB2_21") (pintype "bidirectional"))
      (node (ref "JP3") (pin "4") (pinfunction "4_4") (pintype "passive"))
    )
    (net (code "55") (name "/MOSI3") (class "Default")
      (node (ref "IC3") (pin "21") (pinfunction "(MOSI/PCINT2)PB2_21") (pintype "bidirectional"))
      (node (ref "JP4") (pin "4") (pinfunction "4_4") (pintype "passive"))
    )
    (net (code "56") (name "/RST1") (class "Default")
      (node (ref "IC1") (pin "30") (pinfunction "RESET_30") (pintype "input"))
      (node (ref "JP1") (pin "25") (pinfunction "25_25") (pintype "passive"))
      (node (ref "R7") (pin "1") (pinfunction "1_1") (pintype "passive"))
      (node (ref "S2") (pin "1") (pinfunction "1_1") (pintype "passive"))
    )
    (net (code "57") (name "/RST2") (class "Default")
      (node (ref "IC2") (pin "30") (pinfunction "RESET_30") (pintype "input"))
      (node (ref "JP1") (pin "23") (pinfunction "23_23") (pintype "passive"))
      (node (ref "R8") (pin "1") (pinfunction "1_1") (pintype "passive"))
      (node (ref "S3") (pin "1") (pinfunction "1_1") (pintype "passive"))
    )
    (net (code "58") (name "/RST3") (class "Default")
      (node (ref "IC3") (pin "30") (pinfunction "RESET_30") (pintype "input"))
      (node (ref "JP1") (pin "5") (pinfunction "5_5") (pintype "passive"))
      (node (ref "R9") (pin "1") (pinfunction "1_1") (pintype "passive"))
      (node (ref "S4") (pin "1") (pinfunction "1_1") (pintype "passive"))
    )
    (net (code "59") (name "/RX1") (class "Default")
      (node (ref "IC1") (pin "2") (pinfunction "(RXD0/PCIN8)PE0_2") (pintype "bidirectional"))
      (node (ref "JP1") (pin "10") (pinfunction "10_10") (pintype "passive"))
    )
    (net (code "60") (name "/RX2") (class "Default")
      (node (ref "IC2") (pin "2") (pinfunction "(RXD0/PCIN8)PE0_2") (pintype "bidirectional"))
      (node (ref "JP1") (pin "12") (pinfunction "12_12") (pintype "passive"))
    )
    (net (code "61") (name "/RX3") (class "Default")
      (node (ref "IC3") (pin "2") (pinfunction "(RXD0/PCIN8)PE0_2") (pintype "bidirectional"))
      (node (ref "JP1") (pin "1") (pinfunction "1_1") (pintype "passive"))
    )
    (net (code "62") (name "/S11") (class "Default")
      (node (ref "IC1") (pin "1") (pinfunction "(OC0B)PG5_1") (pintype "bidirectional"))
      (node (ref "MIC3") (pin "P$4") (pinfunction "P$4_P$4") (pintype "bidirectional"))
    )
    (net (code "63") (name "/S12") (class "Default")
      (node (ref "IC2") (pin "1") (pinfunction "(OC0B)PG5_1") (pintype "bidirectional"))
      (node (ref "MIC6") (pin "P$4") (pinfunction "P$4_P$4") (pintype "bidirectional"))
    )
    (net (code "64") (name "/S13") (class "Default")
      (node (ref "IC3") (pin "1") (pinfunction "(OC0B)PG5_1") (pintype "bidirectional"))
      (node (ref "MIC7") (pin "P$4") (pinfunction "P$4_P$4") (pintype "bidirectional"))
    )
    (net (code "65") (name "/S21") (class "Default")
      (node (ref "IC1") (pin "5") (pinfunction "(OC3A/AIN1)PE3_5") (pintype "bidirectional"))
      (node (ref "MIC3") (pin "P$1") (pinfunction "P$1_P$1") (pintype "bidirectional"))
    )
    (net (code "66") (name "/S22") (class "Default")
      (node (ref "IC2") (pin "5") (pinfunction "(OC3A/AIN1)PE3_5") (pintype "bidirectional"))
      (node (ref "MIC6") (pin "P$1") (pinfunction "P$1_P$1") (pintype "bidirectional"))
    )
    (net (code "67") (name "/S23") (class "Default")
      (node (ref "IC3") (pin "5") (pinfunction "(OC3A/AIN1)PE3_5") (pintype "bidirectional"))
      (node (ref "MIC7") (pin "P$1") (pinfunction "P$1_P$1") (pintype "bidirectional"))
    )
    (net (code "68") (name "/S31") (class "Default")
      (node (ref "IC1") (pin "15") (pinfunction "PH3(OC4A)_15") (pintype "bidirectional"))
      (node (ref "MIC2") (pin "P$4") (pinfunction "P$4_P$4") (pintype "bidirectional"))
    )
    (net (code "69") (name "/S32") (class "Default")
      (node (ref "IC2") (pin "15") (pinfunction "PH3(OC4A)_15") (pintype "bidirectional"))
      (node (ref "MIC5") (pin "P$4") (pinfunction "P$4_P$4") (pintype "bidirectional"))
    )
    (net (code "70") (name "/S33") (class "Default")
      (node (ref "IC3") (pin "15") (pinfunction "PH3(OC4A)_15") (pintype "bidirectional"))
      (node (ref "MIC8") (pin "P$4") (pinfunction "P$4_P$4") (pintype "bidirectional"))
    )
    (net (code "71") (name "/S41") (class "Default")
      (node (ref "IC1") (pin "16") (pinfunction "PH4(OC4B)_16") (pintype "bidirectional"))
      (node (ref "MIC2") (pin "P$1") (pinfunction "P$1_P$1") (pintype "bidirectional"))
    )
    (net (code "72") (name "/S42") (class "Default")
      (node (ref "IC2") (pin "16") (pinfunction "PH4(OC4B)_16") (pintype "bidirectional"))
      (node (ref "MIC5") (pin "P$1") (pinfunction "P$1_P$1") (pintype "bidirectional"))
    )
    (net (code "73") (name "/S43") (class "Default")
      (node (ref "IC3") (pin "16") (pinfunction "PH4(OC4B)_16") (pintype "bidirectional"))
      (node (ref "MIC8") (pin "P$1") (pinfunction "P$1_P$1") (pintype "bidirectional"))
    )
    (net (code "74") (name "/S51") (class "Default")
      (node (ref "IC1") (pin "17") (pinfunction "PH5(OC4C)_17") (pintype "bidirectional"))
      (node (ref "MIC1") (pin "P$4") (pinfunction "P$4_P$4") (pintype "bidirectional"))
    )
    (net (code "75") (name "/S52") (class "Default")
      (node (ref "IC2") (pin "17") (pinfunction "PH5(OC4C)_17") (pintype "bidirectional"))
      (node (ref "MIC4") (pin "P$4") (pinfunction "P$4_P$4") (pintype "bidirectional"))
    )
    (net (code "76") (name "/S53") (class "Default")
      (node (ref "IC3") (pin "17") (pinfunction "PH5(OC4C)_17") (pintype "bidirectional"))
      (node (ref "MIC9") (pin "P$4") (pinfunction "P$4_P$4") (pintype "bidirectional"))
    )
    (net (code "77") (name "/S61") (class "Default")
      (node (ref "IC1") (pin "18") (pinfunction "PH6(OC2B)_18") (pintype "bidirectional"))
      (node (ref "MIC1") (pin "P$1") (pinfunction "P$1_P$1") (pintype "bidirectional"))
    )
    (net (code "78") (name "/S62") (class "Default")
      (node (ref "IC2") (pin "18") (pinfunction "PH6(OC2B)_18") (pintype "bidirectional"))
      (node (ref "MIC4") (pin "P$1") (pinfunction "P$1_P$1") (pintype "bidirectional"))
    )
    (net (code "79") (name "/S63") (class "Default")
      (node (ref "IC3") (pin "18") (pinfunction "PH6(OC2B)_18") (pintype "bidirectional"))
      (node (ref "MIC9") (pin "P$1") (pinfunction "P$1_P$1") (pintype "bidirectional"))
    )
    (net (code "80") (name "/SS1") (class "Default")
      (node (ref "IC1") (pin "19") (pinfunction "(SS/PCINT0)PB0_19") (pintype "bidirectional"))
      (node (ref "JP1") (pin "30") (pinfunction "30_30") (pintype "passive"))
    )
    (net (code "81") (name "/SS2") (class "Default")
      (node (ref "IC2") (pin "19") (pinfunction "(SS/PCINT0)PB0_19") (pintype "bidirectional"))
      (node (ref "JP1") (pin "19") (pinfunction "19_19") (pintype "passive"))
    )
    (net (code "82") (name "/SS3") (class "Default")
      (node (ref "IC3") (pin "19") (pinfunction "(SS/PCINT0)PB0_19") (pintype "bidirectional"))
      (node (ref "JP1") (pin "17") (pinfunction "17_17") (pintype "passive"))
    )
    (net (code "83") (name "/TX1") (class "Default")
      (node (ref "IC1") (pin "3") (pinfunction "(TXD0)PE1_3") (pintype "bidirectional"))
      (node (ref "JP1") (pin "11") (pinfunction "11_11") (pintype "passive"))
    )
    (net (code "84") (name "/TX2") (class "Default")
      (node (ref "IC2") (pin "3") (pinfunction "(TXD0)PE1_3") (pintype "bidirectional"))
      (node (ref "JP1") (pin "9") (pinfunction "9_9") (pintype "passive"))
    )
    (net (code "85") (name "/TX3") (class "Default")
      (node (ref "IC3") (pin "3") (pinfunction "(TXD0)PE1_3") (pintype "bidirectional"))
      (node (ref "JP1") (pin "3") (pinfunction "3_3") (pintype "passive"))
    )
    (net (code "86") (name "Net-(C9-Pad1)") (class "Default")
      (node (ref "C9") (pin "1") (pinfunction "1_1") (pintype "passive"))
      (node (ref "S3") (pin "2") (pinfunction "2_2") (pintype "passive"))
    )
    (net (code "87") (name "Net-(C10-Pad1)") (class "Default")
      (node (ref "C10") (pin "1") (pinfunction "1_1") (pintype "passive"))
      (node (ref "S2") (pin "2") (pinfunction "2_2") (pintype "passive"))
    )
    (net (code "88") (name "Net-(C11-Pad1)") (class "Default")
      (node (ref "C11") (pin "1") (pinfunction "1_1") (pintype "passive"))
      (node (ref "S4") (pin "2") (pinfunction "2_2") (pintype "passive"))
    )
    (net (code "89") (name "Net-(D1-PadC)") (class "Default")
      (node (ref "D1") (pin "C") (pinfunction "C_C") (pintype "passive"))
      (node (ref "R1") (pin "1") (pinfunction "1_1") (pintype "passive"))
    )
    (net (code "90") (name "Net-(D2-PadC)") (class "Default")
      (node (ref "D2") (pin "C") (pinfunction "C_C") (pintype "passive"))
      (node (ref "R3") (pin "1") (pinfunction "1_1") (pintype "passive"))
    )
    (net (code "91") (name "Net-(D3-PadC)") (class "Default")
      (node (ref "D3") (pin "C") (pinfunction "C_C") (pintype "passive"))
      (node (ref "R4") (pin "1") (pinfunction "1_1") (pintype "passive"))
    )
    (net (code "92") (name "Net-(D7-PadC)") (class "Default")
      (node (ref "D7") (pin "C") (pinfunction "C_C") (pintype "passive"))
      (node (ref "R10") (pin "1") (pinfunction "1_1") (pintype "passive"))
    )
    (net (code "93") (name "Net-(D8-PadC)") (class "Default")
      (node (ref "D8") (pin "C") (pinfunction "C_C") (pintype "passive"))
      (node (ref "R11") (pin "1") (pinfunction "1_1") (pintype "passive"))
    )
    (net (code "94") (name "Net-(D9-PadC)") (class "Default")
      (node (ref "D9") (pin "C") (pinfunction "C_C") (pintype "passive"))
      (node (ref "R12") (pin "1") (pinfunction "1_1") (pintype "passive"))
    )
    (net (code "95") (name "Net-(D11-PadC)") (class "Default")
      (node (ref "D11") (pin "C") (pinfunction "C_C") (pintype "passive"))
      (node (ref "R14") (pin "1") (pinfunction "1_1") (pintype "passive"))
    )
    (net (code "96") (name "Net-(D12-PadC)") (class "Default")
      (node (ref "D12") (pin "C") (pinfunction "C_C") (pintype "passive"))
      (node (ref "R15") (pin "1") (pinfunction "1_1") (pintype "passive"))
    )
    (net (code "97") (name "Net-(D13-PadC)") (class "Default")
      (node (ref "D13") (pin "C") (pinfunction "C_C") (pintype "passive"))
      (node (ref "R16") (pin "1") (pinfunction "1_1") (pintype "passive"))
    )
    (net (code "98") (name "Net-(D15-PadC)") (class "Default")
      (node (ref "D15") (pin "C") (pinfunction "C_C") (pintype "passive"))
      (node (ref "R18") (pin "1") (pinfunction "1_1") (pintype "passive"))
    )
    (net (code "99") (name "Net-(D16-PadC)") (class "Default")
      (node (ref "D16") (pin "C") (pinfunction "C_C") (pintype "passive"))
      (node (ref "R19") (pin "1") (pinfunction "1_1") (pintype "passive"))
    )
    (net (code "100") (name "Net-(D17-PadC)") (class "Default")
      (node (ref "D17") (pin "C") (pinfunction "C_C") (pintype "passive"))
      (node (ref "R20") (pin "1") (pinfunction "1_1") (pintype "passive"))
    )
    (net (code "101") (name "Net-(IC1-XTAL1)") (class "Default")
      (node (ref "C18") (pin "2") (pinfunction "2_2") (pintype "passive"))
      (node (ref "IC1") (pin "34") (pinfunction "XTAL1_34") (pintype "input"))
      (node (ref "Y2") (pin "1") (pinfunction "1_1") (pintype "passive"))
    )
    (net (code "102") (name "Net-(IC1-XTAL2)") (class "Default")
      (node (ref "C19") (pin "2") (pinfunction "2_2") (pintype "passive"))
      (node (ref "IC1") (pin "33") (pinfunction "XTAL2_33") (pintype "output"))
      (node (ref "Y2") (pin "3") (pinfunction "2_3") (pintype "passive"))
    )
    (net (code "103") (name "Net-(IC2-XTAL1)") (class "Default")
      (node (ref "C16") (pin "2") (pinfunction "2_2") (pintype "passive"))
      (node (ref "IC2") (pin "34") (pinfunction "XTAL1_34") (pintype "input"))
      (node (ref "Y3") (pin "1") (pinfunction "1_1") (pintype "passive"))
    )
    (net (code "104") (name "Net-(IC2-XTAL2)") (class "Default")
      (node (ref "C17") (pin "2") (pinfunction "2_2") (pintype "passive"))
      (node (ref "IC2") (pin "33") (pinfunction "XTAL2_33") (pintype "output"))
      (node (ref "Y3") (pin "3") (pinfunction "2_3") (pintype "passive"))
    )
    (net (code "105") (name "Net-(IC3-XTAL1)") (class "Default")
      (node (ref "C12") (pin "2") (pinfunction "2_2") (pintype "passive"))
      (node (ref "IC3") (pin "34") (pinfunction "XTAL1_34") (pintype "input"))
      (node (ref "Y4") (pin "1") (pinfunction "1_1") (pintype "passive"))
    )
    (net (code "106") (name "Net-(IC3-XTAL2)") (class "Default")
      (node (ref "C13") (pin "2") (pinfunction "2_2") (pintype "passive"))
      (node (ref "IC3") (pin "33") (pinfunction "XTAL2_33") (pintype "output"))
      (node (ref "Y4") (pin "3") (pinfunction "2_3") (pintype "passive"))
    )
    (net (code "107") (name "Net-(IC4-FILTER)") (class "Default")
      (node (ref "C8") (pin "1") (pinfunction "1_1") (pintype "passive"))
      (node (ref "IC4") (pin "6") (pinfunction "FILTER_6") (pintype "bidirectional"))
    )
    (net (code "108") (name "Net-(IC5-FILTER)") (class "Default")
      (node (ref "C23") (pin "1") (pinfunction "1_1") (pintype "passive"))
      (node (ref "IC5") (pin "6") (pinfunction "FILTER_6") (pintype "bidirectional"))
    )
    (net (code "109") (name "Net-(IC6-FILTER)") (class "Default")
      (node (ref "C24") (pin "1") (pinfunction "1_1") (pintype "passive"))
      (node (ref "IC6") (pin "6") (pinfunction "FILTER_6") (pintype "bidirectional"))
    )
    (net (code "110") (name "unconnected-(FRC1-Pad2)") (class "Default")
      (node (ref "FRC1") (pin "2") (pinfunction "2_2") (pintype "passive"))
    )
    (net (code "111") (name "unconnected-(FRC1-Pad3)") (class "Default")
      (node (ref "FRC1") (pin "3") (pinfunction "3_3") (pintype "passive"))
    )
    (net (code "112") (name "unconnected-(FRC1-Pad6)") (class "Default")
      (node (ref "FRC1") (pin "6") (pinfunction "6_6") (pintype "passive"))
    )
    (net (code "113") (name "unconnected-(FRC1-Pad8)") (class "Default")
      (node (ref "FRC1") (pin "8") (pinfunction "8_8") (pintype "passive"))
    )
    (net (code "114") (name "unconnected-(FRC1-Pad9)") (class "Default")
      (node (ref "FRC1") (pin "9") (pinfunction "9_9") (pintype "passive"))
    )
    (net (code "115") (name "unconnected-(FRC1-Pad10)") (class "Default")
      (node (ref "FRC1") (pin "10") (pinfunction "10_10") (pintype "passive"))
    )
    (net (code "116") (name "unconnected-(FRC2-Pad2)") (class "Default")
      (node (ref "FRC2") (pin "2") (pinfunction "2_2") (pintype "passive"))
    )
    (net (code "117") (name "unconnected-(FRC2-Pad3)") (class "Default")
      (node (ref "FRC2") (pin "3") (pinfunction "3_3") (pintype "passive"))
    )
    (net (code "118") (name "unconnected-(FRC2-Pad6)") (class "Default")
      (node (ref "FRC2") (pin "6") (pinfunction "6_6") (pintype "passive"))
    )
    (net (code "119") (name "unconnected-(FRC2-Pad8)") (class "Default")
      (node (ref "FRC2") (pin "8") (pinfunction "8_8") (pintype "passive"))
    )
    (net (code "120") (name "unconnected-(FRC2-Pad9)") (class "Default")
      (node (ref "FRC2") (pin "9") (pinfunction "9_9") (pintype "passive"))
    )
    (net (code "121") (name "unconnected-(FRC2-Pad10)") (class "Default")
      (node (ref "FRC2") (pin "10") (pinfunction "10_10") (pintype "passive"))
    )
    (net (code "122") (name "unconnected-(FRC3-Pad2)") (class "Default")
      (node (ref "FRC3") (pin "2") (pinfunction "2_2") (pintype "passive"))
    )
    (net (code "123") (name "unconnected-(FRC3-Pad3)") (class "Default")
      (node (ref "FRC3") (pin "3") (pinfunction "3_3") (pintype "passive"))
    )
    (net (code "124") (name "unconnected-(FRC3-Pad6)") (class "Default")
      (node (ref "FRC3") (pin "6") (pinfunction "6_6") (pintype "passive"))
    )
    (net (code "125") (name "unconnected-(FRC3-Pad8)") (class "Default")
      (node (ref "FRC3") (pin "8") (pinfunction "8_8") (pintype "passive"))
    )
    (net (code "126") (name "unconnected-(FRC3-Pad9)") (class "Default")
      (node (ref "FRC3") (pin "9") (pinfunction "9_9") (pintype "passive"))
    )
    (net (code "127") (name "unconnected-(FRC3-Pad10)") (class "Default")
      (node (ref "FRC3") (pin "10") (pinfunction "10_10") (pintype "passive"))
    )
    (net (code "128") (name "unconnected-(IC1-(A8)PC0-Pad53)") (class "Default")
      (node (ref "IC1") (pin "53") (pinfunction "(A8)PC0_53") (pintype "bidirectional"))
    )
    (net (code "129") (name "unconnected-(IC1-(A9)PC1-Pad54)") (class "Default")
      (node (ref "IC1") (pin "54") (pinfunction "(A9)PC1_54") (pintype "bidirectional"))
    )
    (net (code "130") (name "unconnected-(IC1-(A10)PC2-Pad55)") (class "Default")
      (node (ref "IC1") (pin "55") (pinfunction "(A10)PC2_55") (pintype "bidirectional"))
    )
    (net (code "131") (name "unconnected-(IC1-(A11)PC3-Pad56)") (class "Default")
      (node (ref "IC1") (pin "56") (pinfunction "(A11)PC3_56") (pintype "bidirectional"))
    )
    (net (code "132") (name "unconnected-(IC1-(A12)PC4-Pad57)") (class "Default")
      (node (ref "IC1") (pin "57") (pinfunction "(A12)PC4_57") (pintype "bidirectional"))
    )
    (net (code "133") (name "unconnected-(IC1-(A13)PC5-Pad58)") (class "Default")
      (node (ref "IC1") (pin "58") (pinfunction "(A13)PC5_58") (pintype "bidirectional"))
    )
    (net (code "134") (name "unconnected-(IC1-(A14)PC6-Pad59)") (class "Default")
      (node (ref "IC1") (pin "59") (pinfunction "(A14)PC6_59") (pintype "bidirectional"))
    )
    (net (code "135") (name "unconnected-(IC1-(A15)PC7-Pad60)") (class "Default")
      (node (ref "IC1") (pin "60") (pinfunction "(A15)PC7_60") (pintype "bidirectional"))
    )
    (net (code "136") (name "unconnected-(IC1-(AD0)PA0-Pad78)") (class "Default")
      (node (ref "IC1") (pin "78") (pinfunction "(AD0)PA0_78") (pintype "bidirectional"))
    )
    (net (code "137") (name "unconnected-(IC1-(AD1)PA1-Pad77)") (class "Default")
      (node (ref "IC1") (pin "77") (pinfunction "(AD1)PA1_77") (pintype "bidirectional"))
    )
    (net (code "138") (name "unconnected-(IC1-(AD2)PA2-Pad76)") (class "Default")
      (node (ref "IC1") (pin "76") (pinfunction "(AD2)PA2_76") (pintype "bidirectional"))
    )
    (net (code "139") (name "unconnected-(IC1-(AD3)PA3-Pad75)") (class "Default")
      (node (ref "IC1") (pin "75") (pinfunction "(AD3)PA3_75") (pintype "bidirectional"))
    )
    (net (code "140") (name "unconnected-(IC1-(AD4)PA4-Pad74)") (class "Default")
      (node (ref "IC1") (pin "74") (pinfunction "(AD4)PA4_74") (pintype "bidirectional"))
    )
    (net (code "141") (name "unconnected-(IC1-(AD5)PA5-Pad73)") (class "Default")
      (node (ref "IC1") (pin "73") (pinfunction "(AD5)PA5_73") (pintype "bidirectional"))
    )
    (net (code "142") (name "unconnected-(IC1-(AD6)PA6-Pad72)") (class "Default")
      (node (ref "IC1") (pin "72") (pinfunction "(AD6)PA6_72") (pintype "bidirectional"))
    )
    (net (code "143") (name "unconnected-(IC1-(AD7)PA7-Pad71)") (class "Default")
      (node (ref "IC1") (pin "71") (pinfunction "(AD7)PA7_71") (pintype "bidirectional"))
    )
    (net (code "144") (name "unconnected-(IC1-(ADC1)PF1-Pad96)") (class "Default")
      (node (ref "IC1") (pin "96") (pinfunction "(ADC1)PF1_96") (pintype "bidirectional"))
    )
    (net (code "145") (name "unconnected-(IC1-(ADC2)PF2-Pad95)") (class "Default")
      (node (ref "IC1") (pin "95") (pinfunction "(ADC2)PF2_95") (pintype "bidirectional"))
    )
    (net (code "146") (name "unconnected-(IC1-(ADC3)PF3-Pad94)") (class "Default")
      (node (ref "IC1") (pin "94") (pinfunction "(ADC3)PF3_94") (pintype "bidirectional"))
    )
    (net (code "147") (name "unconnected-(IC1-(ADC4{slash}TCK)PF4-Pad93)") (class "Default")
      (node (ref "IC1") (pin "93") (pinfunction "(ADC4/TCK)PF4_93") (pintype "bidirectional"))
    )
    (net (code "148") (name "unconnected-(IC1-(ADC5{slash}TMS)PF5-Pad92)") (class "Default")
      (node (ref "IC1") (pin "92") (pinfunction "(ADC5/TMS)PF5_92") (pintype "bidirectional"))
    )
    (net (code "149") (name "unconnected-(IC1-(ADC6{slash}TDO)PF6-Pad91)") (class "Default")
      (node (ref "IC1") (pin "91") (pinfunction "(ADC6/TDO)PF6_91") (pintype "bidirectional"))
    )
    (net (code "150") (name "unconnected-(IC1-(ADC7{slash}TDI)PF7-Pad90)") (class "Default")
      (node (ref "IC1") (pin "90") (pinfunction "(ADC7/TDI)PF7_90") (pintype "bidirectional"))
    )
    (net (code "151") (name "unconnected-(IC1-(ALE)PG2-Pad70)") (class "Default")
      (node (ref "IC1") (pin "70") (pinfunction "(ALE)PG2_70") (pintype "bidirectional"))
    )
    (net (code "152") (name "unconnected-(IC1-(CLKO{slash}ICP3{slash}INT7)PE7-Pad9)") (class "Default")
      (node (ref "IC1") (pin "9") (pinfunction "(CLKO/ICP3/INT7)PE7_9") (pintype "bidirectional"))
    )
    (net (code "153") (name "unconnected-(IC1-(ICP1)PD4-Pad47)") (class "Default")
      (node (ref "IC1") (pin "47") (pinfunction "(ICP1)PD4_47") (pintype "bidirectional"))
    )
    (net (code "154") (name "unconnected-(IC1-(OC0A{slash}OC1C{slash}PCINT7)PB7-Pad26)") (class "Default")
      (node (ref "IC1") (pin "26") (pinfunction "(OC0A/OC1C/PCINT7)PB7_26") (pintype "bidirectional"))
    )
    (net (code "155") (name "unconnected-(IC1-(OC3B{slash}INT4)PE4-Pad6)") (class "Default")
      (node (ref "IC1") (pin "6") (pinfunction "(OC3B/INT4)PE4_6") (pintype "bidirectional"))
    )
    (net (code "156") (name "unconnected-(IC1-(RD)PG1-Pad52)") (class "Default")
      (node (ref "IC1") (pin "52") (pinfunction "(RD)PG1_52") (pintype "bidirectional"))
    )
    (net (code "157") (name "unconnected-(IC1-(T0)PD7-Pad50)") (class "Default")
      (node (ref "IC1") (pin "50") (pinfunction "(T0)PD7_50") (pintype "bidirectional"))
    )
    (net (code "158") (name "unconnected-(IC1-(T1)PD6-Pad49)") (class "Default")
      (node (ref "IC1") (pin "49") (pinfunction "(T1)PD6_49") (pintype "bidirectional"))
    )
    (net (code "159") (name "unconnected-(IC1-(T3{slash}INT6)PE6-Pad8)") (class "Default")
      (node (ref "IC1") (pin "8") (pinfunction "(T3/INT6)PE6_8") (pintype "bidirectional"))
    )
    (net (code "160") (name "unconnected-(IC1-(TOSC1)PG4-Pad29)") (class "Default")
      (node (ref "IC1") (pin "29") (pinfunction "(TOSC1)PG4_29") (pintype "bidirectional"))
    )
    (net (code "161") (name "unconnected-(IC1-(TOSC2)PG3-Pad28)") (class "Default")
      (node (ref "IC1") (pin "28") (pinfunction "(TOSC2)PG3_28") (pintype "bidirectional"))
    )
    (net (code "162") (name "unconnected-(IC1-(WR)PG0-Pad51)") (class "Default")
      (node (ref "IC1") (pin "51") (pinfunction "(WR)PG0_51") (pintype "bidirectional"))
    )
    (net (code "163") (name "unconnected-(IC1-(XCK0{slash}AIN0)PE2-Pad4)") (class "Default")
      (node (ref "IC1") (pin "4") (pinfunction "(XCK0/AIN0)PE2_4") (pintype "bidirectional"))
    )
    (net (code "164") (name "unconnected-(IC1-(XCK1)PD5-Pad48)") (class "Default")
      (node (ref "IC1") (pin "48") (pinfunction "(XCK1)PD5_48") (pintype "bidirectional"))
    )
    (net (code "165") (name "unconnected-(IC1-PH0(RXD2)-Pad12)") (class "Default")
      (node (ref "IC1") (pin "12") (pinfunction "PH0(RXD2)_12") (pintype "bidirectional"))
    )
    (net (code "166") (name "unconnected-(IC1-PH1(TXD2)-Pad13)") (class "Default")
      (node (ref "IC1") (pin "13") (pinfunction "PH1(TXD2)_13") (pintype "bidirectional"))
    )
    (net (code "167") (name "unconnected-(IC1-PH2(XCK2)-Pad14)") (class "Default")
      (node (ref "IC1") (pin "14") (pinfunction "PH2(XCK2)_14") (pintype "bidirectional"))
    )
    (net (code "168") (name "unconnected-(IC1-PH7(T4)-Pad27)") (class "Default")
      (node (ref "IC1") (pin "27") (pinfunction "PH7(T4)_27") (pintype "bidirectional"))
    )
    (net (code "169") (name "unconnected-(IC1-PJ0(RXD3{slash}PCINT9)-Pad63)") (class "Default")
      (node (ref "IC1") (pin "63") (pinfunction "PJ0(RXD3/PCINT9)_63") (pintype "bidirectional"))
    )
    (net (code "170") (name "unconnected-(IC1-PJ1(TXD3{slash}PCINT10)-Pad64)") (class "Default")
      (node (ref "IC1") (pin "64") (pinfunction "PJ1(TXD3/PCINT10)_64") (pintype "bidirectional"))
    )
    (net (code "171") (name "unconnected-(IC1-PJ2(XCK3{slash}PCINT11)-Pad65)") (class "Default")
      (node (ref "IC1") (pin "65") (pinfunction "PJ2(XCK3/PCINT11)_65") (pintype "bidirectional"))
    )
    (net (code "172") (name "unconnected-(IC1-PJ3(PCINT12)-Pad66)") (class "Default")
      (node (ref "IC1") (pin "66") (pinfunction "PJ3(PCINT12)_66") (pintype "bidirectional"))
    )
    (net (code "173") (name "unconnected-(IC1-PJ4(PCINT13)-Pad67)") (class "Default")
      (node (ref "IC1") (pin "67") (pinfunction "PJ4(PCINT13)_67") (pintype "bidirectional"))
    )
    (net (code "174") (name "unconnected-(IC1-PJ5(PCINT14)-Pad68)") (class "Default")
      (node (ref "IC1") (pin "68") (pinfunction "PJ5(PCINT14)_68") (pintype "bidirectional"))
    )
    (net (code "175") (name "unconnected-(IC1-PJ6(PCINT15)-Pad69)") (class "Default")
      (node (ref "IC1") (pin "69") (pinfunction "PJ6(PCINT15)_69") (pintype "bidirectional"))
    )
    (net (code "176") (name "unconnected-(IC1-PJ7-Pad79)") (class "Default")
      (node (ref "IC1") (pin "79") (pinfunction "PJ7_79") (pintype "bidirectional"))
    )
    (net (code "177") (name "unconnected-(IC1-PK0(ADC8{slash}PCINT16)-Pad89)") (class "Default")
      (node (ref "IC1") (pin "89") (pinfunction "PK0(ADC8/PCINT16)_89") (pintype "bidirectional"))
    )
    (net (code "178") (name "unconnected-(IC1-PK1(ADC9{slash}PCINT17)-Pad88)") (class "Default")
      (node (ref "IC1") (pin "88") (pinfunction "PK1(ADC9/PCINT17)_88") (pintype "bidirectional"))
    )
    (net (code "179") (name "unconnected-(IC1-PK2(ADC10{slash}PCINT18)-Pad87)") (class "Default")
      (node (ref "IC1") (pin "87") (pinfunction "PK2(ADC10/PCINT18)_87") (pintype "bidirectional"))
    )
    (net (code "180") (name "unconnected-(IC1-PK3(ADC11{slash}PCINT19)-Pad86)") (class "Default")
      (node (ref "IC1") (pin "86") (pinfunction "PK3(ADC11/PCINT19)_86") (pintype "bidirectional"))
    )
    (net (code "181") (name "unconnected-(IC1-PK4(ADC12{slash}PCINT20)-Pad85)") (class "Default")
      (node (ref "IC1") (pin "85") (pinfunction "PK4(ADC12/PCINT20)_85") (pintype "bidirectional"))
    )
    (net (code "182") (name "unconnected-(IC1-PK5(ADC13{slash}PCINT21)-Pad84)") (class "Default")
      (node (ref "IC1") (pin "84") (pinfunction "PK5(ADC13/PCINT21)_84") (pintype "bidirectional"))
    )
    (net (code "183") (name "unconnected-(IC1-PK6(ADC14{slash}PCINT22)-Pad83)") (class "Default")
      (node (ref "IC1") (pin "83") (pinfunction "PK6(ADC14/PCINT22)_83") (pintype "bidirectional"))
    )
    (net (code "184") (name "unconnected-(IC1-PK7(ADC15{slash}PCINT23)-Pad82)") (class "Default")
      (node (ref "IC1") (pin "82") (pinfunction "PK7(ADC15/PCINT23)_82") (pintype "bidirectional"))
    )
    (net (code "185") (name "unconnected-(IC1-PL0(ICP4)-Pad35)") (class "Default")
      (node (ref "IC1") (pin "35") (pinfunction "PL0(ICP4)_35") (pintype "bidirectional"))
    )
    (net (code "186") (name "unconnected-(IC1-PL1(ICP5)-Pad36)") (class "Default")
      (node (ref "IC1") (pin "36") (pinfunction "PL1(ICP5)_36") (pintype "bidirectional"))
    )
    (net (code "187") (name "unconnected-(IC1-PL2(T5)-Pad37)") (class "Default")
      (node (ref "IC1") (pin "37") (pinfunction "PL2(T5)_37") (pintype "bidirectional"))
    )
    (net (code "188") (name "unconnected-(IC1-PL3(OC5A)-Pad38)") (class "Default")
      (node (ref "IC1") (pin "38") (pinfunction "PL3(OC5A)_38") (pintype "bidirectional"))
    )
    (net (code "189") (name "unconnected-(IC1-PL4(OC5B)-Pad39)") (class "Default")
      (node (ref "IC1") (pin "39") (pinfunction "PL4(OC5B)_39") (pintype "bidirectional"))
    )
    (net (code "190") (name "unconnected-(IC1-PL5(OC5C)-Pad40)") (class "Default")
      (node (ref "IC1") (pin "40") (pinfunction "PL5(OC5C)_40") (pintype "bidirectional"))
    )
    (net (code "191") (name "unconnected-(IC1-PL6-Pad41)") (class "Default")
      (node (ref "IC1") (pin "41") (pinfunction "PL6_41") (pintype "bidirectional"))
    )
    (net (code "192") (name "unconnected-(IC1-PL7-Pad42)") (class "Default")
      (node (ref "IC1") (pin "42") (pinfunction "PL7_42") (pintype "bidirectional"))
    )
    (net (code "193") (name "unconnected-(IC2-(A8)PC0-Pad53)") (class "Default")
      (node (ref "IC2") (pin "53") (pinfunction "(A8)PC0_53") (pintype "bidirectional"))
    )
    (net (code "194") (name "unconnected-(IC2-(A9)PC1-Pad54)") (class "Default")
      (node (ref "IC2") (pin "54") (pinfunction "(A9)PC1_54") (pintype "bidirectional"))
    )
    (net (code "195") (name "unconnected-(IC2-(A10)PC2-Pad55)") (class "Default")
      (node (ref "IC2") (pin "55") (pinfunction "(A10)PC2_55") (pintype "bidirectional"))
    )
    (net (code "196") (name "unconnected-(IC2-(A11)PC3-Pad56)") (class "Default")
      (node (ref "IC2") (pin "56") (pinfunction "(A11)PC3_56") (pintype "bidirectional"))
    )
    (net (code "197") (name "unconnected-(IC2-(A12)PC4-Pad57)") (class "Default")
      (node (ref "IC2") (pin "57") (pinfunction "(A12)PC4_57") (pintype "bidirectional"))
    )
    (net (code "198") (name "unconnected-(IC2-(A13)PC5-Pad58)") (class "Default")
      (node (ref "IC2") (pin "58") (pinfunction "(A13)PC5_58") (pintype "bidirectional"))
    )
    (net (code "199") (name "unconnected-(IC2-(A14)PC6-Pad59)") (class "Default")
      (node (ref "IC2") (pin "59") (pinfunction "(A14)PC6_59") (pintype "bidirectional"))
    )
    (net (code "200") (name "unconnected-(IC2-(A15)PC7-Pad60)") (class "Default")
      (node (ref "IC2") (pin "60") (pinfunction "(A15)PC7_60") (pintype "bidirectional"))
    )
    (net (code "201") (name "unconnected-(IC2-(AD0)PA0-Pad78)") (class "Default")
      (node (ref "IC2") (pin "78") (pinfunction "(AD0)PA0_78") (pintype "bidirectional"))
    )
    (net (code "202") (name "unconnected-(IC2-(AD1)PA1-Pad77)") (class "Default")
      (node (ref "IC2") (pin "77") (pinfunction "(AD1)PA1_77") (pintype "bidirectional"))
    )
    (net (code "203") (name "unconnected-(IC2-(AD2)PA2-Pad76)") (class "Default")
      (node (ref "IC2") (pin "76") (pinfunction "(AD2)PA2_76") (pintype "bidirectional"))
    )
    (net (code "204") (name "unconnected-(IC2-(AD3)PA3-Pad75)") (class "Default")
      (node (ref "IC2") (pin "75") (pinfunction "(AD3)PA3_75") (pintype "bidirectional"))
    )
    (net (code "205") (name "unconnected-(IC2-(AD4)PA4-Pad74)") (class "Default")
      (node (ref "IC2") (pin "74") (pinfunction "(AD4)PA4_74") (pintype "bidirectional"))
    )
    (net (code "206") (name "unconnected-(IC2-(AD5)PA5-Pad73)") (class "Default")
      (node (ref "IC2") (pin "73") (pinfunction "(AD5)PA5_73") (pintype "bidirectional"))
    )
    (net (code "207") (name "unconnected-(IC2-(AD6)PA6-Pad72)") (class "Default")
      (node (ref "IC2") (pin "72") (pinfunction "(AD6)PA6_72") (pintype "bidirectional"))
    )
    (net (code "208") (name "unconnected-(IC2-(AD7)PA7-Pad71)") (class "Default")
      (node (ref "IC2") (pin "71") (pinfunction "(AD7)PA7_71") (pintype "bidirectional"))
    )
    (net (code "209") (name "unconnected-(IC2-(ADC1)PF1-Pad96)") (class "Default")
      (node (ref "IC2") (pin "96") (pinfunction "(ADC1)PF1_96") (pintype "bidirectional"))
    )
    (net (code "210") (name "unconnected-(IC2-(ADC2)PF2-Pad95)") (class "Default")
      (node (ref "IC2") (pin "95") (pinfunction "(ADC2)PF2_95") (pintype "bidirectional"))
    )
    (net (code "211") (name "unconnected-(IC2-(ADC3)PF3-Pad94)") (class "Default")
      (node (ref "IC2") (pin "94") (pinfunction "(ADC3)PF3_94") (pintype "bidirectional"))
    )
    (net (code "212") (name "unconnected-(IC2-(ADC4{slash}TCK)PF4-Pad93)") (class "Default")
      (node (ref "IC2") (pin "93") (pinfunction "(ADC4/TCK)PF4_93") (pintype "bidirectional"))
    )
    (net (code "213") (name "unconnected-(IC2-(ADC5{slash}TMS)PF5-Pad92)") (class "Default")
      (node (ref "IC2") (pin "92") (pinfunction "(ADC5/TMS)PF5_92") (pintype "bidirectional"))
    )
    (net (code "214") (name "unconnected-(IC2-(ADC6{slash}TDO)PF6-Pad91)") (class "Default")
      (node (ref "IC2") (pin "91") (pinfunction "(ADC6/TDO)PF6_91") (pintype "bidirectional"))
    )
    (net (code "215") (name "unconnected-(IC2-(ADC7{slash}TDI)PF7-Pad90)") (class "Default")
      (node (ref "IC2") (pin "90") (pinfunction "(ADC7/TDI)PF7_90") (pintype "bidirectional"))
    )
    (net (code "216") (name "unconnected-(IC2-(ALE)PG2-Pad70)") (class "Default")
      (node (ref "IC2") (pin "70") (pinfunction "(ALE)PG2_70") (pintype "bidirectional"))
    )
    (net (code "217") (name "unconnected-(IC2-(CLKO{slash}ICP3{slash}INT7)PE7-Pad9)") (class "Default")
      (node (ref "IC2") (pin "9") (pinfunction "(CLKO/ICP3/INT7)PE7_9") (pintype "bidirectional"))
    )
    (net (code "218") (name "unconnected-(IC2-(ICP1)PD4-Pad47)") (class "Default")
      (node (ref "IC2") (pin "47") (pinfunction "(ICP1)PD4_47") (pintype "bidirectional"))
    )
    (net (code "219") (name "unconnected-(IC2-(OC0A{slash}OC1C{slash}PCINT7)PB7-Pad26)") (class "Default")
      (node (ref "IC2") (pin "26") (pinfunction "(OC0A/OC1C/PCINT7)PB7_26") (pintype "bidirectional"))
    )
    (net (code "220") (name "unconnected-(IC2-(OC3B{slash}INT4)PE4-Pad6)") (class "Default")
      (node (ref "IC2") (pin "6") (pinfunction "(OC3B/INT4)PE4_6") (pintype "bidirectional"))
    )
    (net (code "221") (name "unconnected-(IC2-(RD)PG1-Pad52)") (class "Default")
      (node (ref "IC2") (pin "52") (pinfunction "(RD)PG1_52") (pintype "bidirectional"))
    )
    (net (code "222") (name "unconnected-(IC2-(T0)PD7-Pad50)") (class "Default")
      (node (ref "IC2") (pin "50") (pinfunction "(T0)PD7_50") (pintype "bidirectional"))
    )
    (net (code "223") (name "unconnected-(IC2-(T1)PD6-Pad49)") (class "Default")
      (node (ref "IC2") (pin "49") (pinfunction "(T1)PD6_49") (pintype "bidirectional"))
    )
    (net (code "224") (name "unconnected-(IC2-(T3{slash}INT6)PE6-Pad8)") (class "Default")
      (node (ref "IC2") (pin "8") (pinfunction "(T3/INT6)PE6_8") (pintype "bidirectional"))
    )
    (net (code "225") (name "unconnected-(IC2-(TOSC1)PG4-Pad29)") (class "Default")
      (node (ref "IC2") (pin "29") (pinfunction "(TOSC1)PG4_29") (pintype "bidirectional"))
    )
    (net (code "226") (name "unconnected-(IC2-(TOSC2)PG3-Pad28)") (class "Default")
      (node (ref "IC2") (pin "28") (pinfunction "(TOSC2)PG3_28") (pintype "bidirectional"))
    )
    (net (code "227") (name "unconnected-(IC2-(WR)PG0-Pad51)") (class "Default")
      (node (ref "IC2") (pin "51") (pinfunction "(WR)PG0_51") (pintype "bidirectional"))
    )
    (net (code "228") (name "unconnected-(IC2-(XCK0{slash}AIN0)PE2-Pad4)") (class "Default")
      (node (ref "IC2") (pin "4") (pinfunction "(XCK0/AIN0)PE2_4") (pintype "bidirectional"))
    )
    (net (code "229") (name "unconnected-(IC2-(XCK1)PD5-Pad48)") (class "Default")
      (node (ref "IC2") (pin "48") (pinfunction "(XCK1)PD5_48") (pintype "bidirectional"))
    )
    (net (code "230") (name "unconnected-(IC2-PH0(RXD2)-Pad12)") (class "Default")
      (node (ref "IC2") (pin "12") (pinfunction "PH0(RXD2)_12") (pintype "bidirectional"))
    )
    (net (code "231") (name "unconnected-(IC2-PH1(TXD2)-Pad13)") (class "Default")
      (node (ref "IC2") (pin "13") (pinfunction "PH1(TXD2)_13") (pintype "bidirectional"))
    )
    (net (code "232") (name "unconnected-(IC2-PH2(XCK2)-Pad14)") (class "Default")
      (node (ref "IC2") (pin "14") (pinfunction "PH2(XCK2)_14") (pintype "bidirectional"))
    )
    (net (code "233") (name "unconnected-(IC2-PH7(T4)-Pad27)") (class "Default")
      (node (ref "IC2") (pin "27") (pinfunction "PH7(T4)_27") (pintype "bidirectional"))
    )
    (net (code "234") (name "unconnected-(IC2-PJ0(RXD3{slash}PCINT9)-Pad63)") (class "Default")
      (node (ref "IC2") (pin "63") (pinfunction "PJ0(RXD3/PCINT9)_63") (pintype "bidirectional"))
    )
    (net (code "235") (name "unconnected-(IC2-PJ1(TXD3{slash}PCINT10)-Pad64)") (class "Default")
      (node (ref "IC2") (pin "64") (pinfunction "PJ1(TXD3/PCINT10)_64") (pintype "bidirectional"))
    )
    (net (code "236") (name "unconnected-(IC2-PJ2(XCK3{slash}PCINT11)-Pad65)") (class "Default")
      (node (ref "IC2") (pin "65") (pinfunction "PJ2(XCK3/PCINT11)_65") (pintype "bidirectional"))
    )
    (net (code "237") (name "unconnected-(IC2-PJ3(PCINT12)-Pad66)") (class "Default")
      (node (ref "IC2") (pin "66") (pinfunction "PJ3(PCINT12)_66") (pintype "bidirectional"))
    )
    (net (code "238") (name "unconnected-(IC2-PJ4(PCINT13)-Pad67)") (class "Default")
      (node (ref "IC2") (pin "67") (pinfunction "PJ4(PCINT13)_67") (pintype "bidirectional"))
    )
    (net (code "239") (name "unconnected-(IC2-PJ5(PCINT14)-Pad68)") (class "Default")
      (node (ref "IC2") (pin "68") (pinfunction "PJ5(PCINT14)_68") (pintype "bidirectional"))
    )
    (net (code "240") (name "unconnected-(IC2-PJ6(PCINT15)-Pad69)") (class "Default")
      (node (ref "IC2") (pin "69") (pinfunction "PJ6(PCINT15)_69") (pintype "bidirectional"))
    )
    (net (code "241") (name "unconnected-(IC2-PJ7-Pad79)") (class "Default")
      (node (ref "IC2") (pin "79") (pinfunction "PJ7_79") (pintype "bidirectional"))
    )
    (net (code "242") (name "unconnected-(IC2-PK0(ADC8{slash}PCINT16)-Pad89)") (class "Default")
      (node (ref "IC2") (pin "89") (pinfunction "PK0(ADC8/PCINT16)_89") (pintype "bidirectional"))
    )
    (net (code "243") (name "unconnected-(IC2-PK1(ADC9{slash}PCINT17)-Pad88)") (class "Default")
      (node (ref "IC2") (pin "88") (pinfunction "PK1(ADC9/PCINT17)_88") (pintype "bidirectional"))
    )
    (net (code "244") (name "unconnected-(IC2-PK2(ADC10{slash}PCINT18)-Pad87)") (class "Default")
      (node (ref "IC2") (pin "87") (pinfunction "PK2(ADC10/PCINT18)_87") (pintype "bidirectional"))
    )
    (net (code "245") (name "unconnected-(IC2-PK3(ADC11{slash}PCINT19)-Pad86)") (class "Default")
      (node (ref "IC2") (pin "86") (pinfunction "PK3(ADC11/PCINT19)_86") (pintype "bidirectional"))
    )
    (net (code "246") (name "unconnected-(IC2-PK4(ADC12{slash}PCINT20)-Pad85)") (class "Default")
      (node (ref "IC2") (pin "85") (pinfunction "PK4(ADC12/PCINT20)_85") (pintype "bidirectional"))
    )
    (net (code "247") (name "unconnected-(IC2-PK5(ADC13{slash}PCINT21)-Pad84)") (class "Default")
      (node (ref "IC2") (pin "84") (pinfunction "PK5(ADC13/PCINT21)_84") (pintype "bidirectional"))
    )
    (net (code "248") (name "unconnected-(IC2-PK6(ADC14{slash}PCINT22)-Pad83)") (class "Default")
      (node (ref "IC2") (pin "83") (pinfunction "PK6(ADC14/PCINT22)_83") (pintype "bidirectional"))
    )
    (net (code "249") (name "unconnected-(IC2-PK7(ADC15{slash}PCINT23)-Pad82)") (class "Default")
      (node (ref "IC2") (pin "82") (pinfunction "PK7(ADC15/PCINT23)_82") (pintype "bidirectional"))
    )
    (net (code "250") (name "unconnected-(IC2-PL0(ICP4)-Pad35)") (class "Default")
      (node (ref "IC2") (pin "35") (pinfunction "PL0(ICP4)_35") (pintype "bidirectional"))
    )
    (net (code "251") (name "unconnected-(IC2-PL1(ICP5)-Pad36)") (class "Default")
      (node (ref "IC2") (pin "36") (pinfunction "PL1(ICP5)_36") (pintype "bidirectional"))
    )
    (net (code "252") (name "unconnected-(IC2-PL2(T5)-Pad37)") (class "Default")
      (node (ref "IC2") (pin "37") (pinfunction "PL2(T5)_37") (pintype "bidirectional"))
    )
    (net (code "253") (name "unconnected-(IC2-PL3(OC5A)-Pad38)") (class "Default")
      (node (ref "IC2") (pin "38") (pinfunction "PL3(OC5A)_38") (pintype "bidirectional"))
    )
    (net (code "254") (name "unconnected-(IC2-PL4(OC5B)-Pad39)") (class "Default")
      (node (ref "IC2") (pin "39") (pinfunction "PL4(OC5B)_39") (pintype "bidirectional"))
    )
    (net (code "255") (name "unconnected-(IC2-PL5(OC5C)-Pad40)") (class "Default")
      (node (ref "IC2") (pin "40") (pinfunction "PL5(OC5C)_40") (pintype "bidirectional"))
    )
    (net (code "256") (name "unconnected-(IC2-PL6-Pad41)") (class "Default")
      (node (ref "IC2") (pin "41") (pinfunction "PL6_41") (pintype "bidirectional"))
    )
    (net (code "257") (name "unconnected-(IC2-PL7-Pad42)") (class "Default")
      (node (ref "IC2") (pin "42") (pinfunction "PL7_42") (pintype "bidirectional"))
    )
    (net (code "258") (name "unconnected-(IC3-(A8)PC0-Pad53)") (class "Default")
      (node (ref "IC3") (pin "53") (pinfunction "(A8)PC0_53") (pintype "bidirectional"))
    )
    (net (code "259") (name "unconnected-(IC3-(A9)PC1-Pad54)") (class "Default")
      (node (ref "IC3") (pin "54") (pinfunction "(A9)PC1_54") (pintype "bidirectional"))
    )
    (net (code "260") (name "unconnected-(IC3-(A10)PC2-Pad55)") (class "Default")
      (node (ref "IC3") (pin "55") (pinfunction "(A10)PC2_55") (pintype "bidirectional"))
    )
    (net (code "261") (name "unconnected-(IC3-(A11)PC3-Pad56)") (class "Default")
      (node (ref "IC3") (pin "56") (pinfunction "(A11)PC3_56") (pintype "bidirectional"))
    )
    (net (code "262") (name "unconnected-(IC3-(A12)PC4-Pad57)") (class "Default")
      (node (ref "IC3") (pin "57") (pinfunction "(A12)PC4_57") (pintype "bidirectional"))
    )
    (net (code "263") (name "unconnected-(IC3-(A13)PC5-Pad58)") (class "Default")
      (node (ref "IC3") (pin "58") (pinfunction "(A13)PC5_58") (pintype "bidirectional"))
    )
    (net (code "264") (name "unconnected-(IC3-(A14)PC6-Pad59)") (class "Default")
      (node (ref "IC3") (pin "59") (pinfunction "(A14)PC6_59") (pintype "bidirectional"))
    )
    (net (code "265") (name "unconnected-(IC3-(A15)PC7-Pad60)") (class "Default")
      (node (ref "IC3") (pin "60") (pinfunction "(A15)PC7_60") (pintype "bidirectional"))
    )
    (net (code "266") (name "unconnected-(IC3-(AD0)PA0-Pad78)") (class "Default")
      (node (ref "IC3") (pin "78") (pinfunction "(AD0)PA0_78") (pintype "bidirectional"))
    )
    (net (code "267") (name "unconnected-(IC3-(AD1)PA1-Pad77)") (class "Default")
      (node (ref "IC3") (pin "77") (pinfunction "(AD1)PA1_77") (pintype "bidirectional"))
    )
    (net (code "268") (name "unconnected-(IC3-(AD2)PA2-Pad76)") (class "Default")
      (node (ref "IC3") (pin "76") (pinfunction "(AD2)PA2_76") (pintype "bidirectional"))
    )
    (net (code "269") (name "unconnected-(IC3-(AD3)PA3-Pad75)") (class "Default")
      (node (ref "IC3") (pin "75") (pinfunction "(AD3)PA3_75") (pintype "bidirectional"))
    )
    (net (code "270") (name "unconnected-(IC3-(AD4)PA4-Pad74)") (class "Default")
      (node (ref "IC3") (pin "74") (pinfunction "(AD4)PA4_74") (pintype "bidirectional"))
    )
    (net (code "271") (name "unconnected-(IC3-(AD5)PA5-Pad73)") (class "Default")
      (node (ref "IC3") (pin "73") (pinfunction "(AD5)PA5_73") (pintype "bidirectional"))
    )
    (net (code "272") (name "unconnected-(IC3-(AD6)PA6-Pad72)") (class "Default")
      (node (ref "IC3") (pin "72") (pinfunction "(AD6)PA6_72") (pintype "bidirectional"))
    )
    (net (code "273") (name "unconnected-(IC3-(AD7)PA7-Pad71)") (class "Default")
      (node (ref "IC3") (pin "71") (pinfunction "(AD7)PA7_71") (pintype "bidirectional"))
    )
    (net (code "274") (name "unconnected-(IC3-(ADC1)PF1-Pad96)") (class "Default")
      (node (ref "IC3") (pin "96") (pinfunction "(ADC1)PF1_96") (pintype "bidirectional"))
    )
    (net (code "275") (name "unconnected-(IC3-(ADC2)PF2-Pad95)") (class "Default")
      (node (ref "IC3") (pin "95") (pinfunction "(ADC2)PF2_95") (pintype "bidirectional"))
    )
    (net (code "276") (name "unconnected-(IC3-(ADC3)PF3-Pad94)") (class "Default")
      (node (ref "IC3") (pin "94") (pinfunction "(ADC3)PF3_94") (pintype "bidirectional"))
    )
    (net (code "277") (name "unconnected-(IC3-(ADC4{slash}TCK)PF4-Pad93)") (class "Default")
      (node (ref "IC3") (pin "93") (pinfunction "(ADC4/TCK)PF4_93") (pintype "bidirectional"))
    )
    (net (code "278") (name "unconnected-(IC3-(ADC5{slash}TMS)PF5-Pad92)") (class "Default")
      (node (ref "IC3") (pin "92") (pinfunction "(ADC5/TMS)PF5_92") (pintype "bidirectional"))
    )
    (net (code "279") (name "unconnected-(IC3-(ADC6{slash}TDO)PF6-Pad91)") (class "Default")
      (node (ref "IC3") (pin "91") (pinfunction "(ADC6/TDO)PF6_91") (pintype "bidirectional"))
    )
    (net (code "280") (name "unconnected-(IC3-(ADC7{slash}TDI)PF7-Pad90)") (class "Default")
      (node (ref "IC3") (pin "90") (pinfunction "(ADC7/TDI)PF7_90") (pintype "bidirectional"))
    )
    (net (code "281") (name "unconnected-(IC3-(ALE)PG2-Pad70)") (class "Default")
      (node (ref "IC3") (pin "70") (pinfunction "(ALE)PG2_70") (pintype "bidirectional"))
    )
    (net (code "282") (name "unconnected-(IC3-(CLKO{slash}ICP3{slash}INT7)PE7-Pad9)") (class "Default")
      (node (ref "IC3") (pin "9") (pinfunction "(CLKO/ICP3/INT7)PE7_9") (pintype "bidirectional"))
    )
    (net (code "283") (name "unconnected-(IC3-(ICP1)PD4-Pad47)") (class "Default")
      (node (ref "IC3") (pin "47") (pinfunction "(ICP1)PD4_47") (pintype "bidirectional"))
    )
    (net (code "284") (name "unconnected-(IC3-(OC0A{slash}OC1C{slash}PCINT7)PB7-Pad26)") (class "Default")
      (node (ref "IC3") (pin "26") (pinfunction "(OC0A/OC1C/PCINT7)PB7_26") (pintype "bidirectional"))
    )
    (net (code "285") (name "unconnected-(IC3-(OC3B{slash}INT4)PE4-Pad6)") (class "Default")
      (node (ref "IC3") (pin "6") (pinfunction "(OC3B/INT4)PE4_6") (pintype "bidirectional"))
    )
    (net (code "286") (name "unconnected-(IC3-(RD)PG1-Pad52)") (class "Default")
      (node (ref "IC3") (pin "52") (pinfunction "(RD)PG1_52") (pintype "bidirectional"))
    )
    (net (code "287") (name "unconnected-(IC3-(T0)PD7-Pad50)") (class "Default")
      (node (ref "IC3") (pin "50") (pinfunction "(T0)PD7_50") (pintype "bidirectional"))
    )
    (net (code "288") (name "unconnected-(IC3-(T1)PD6-Pad49)") (class "Default")
      (node (ref "IC3") (pin "49") (pinfunction "(T1)PD6_49") (pintype "bidirectional"))
    )
    (net (code "289") (name "unconnected-(IC3-(T3{slash}INT6)PE6-Pad8)") (class "Default")
      (node (ref "IC3") (pin "8") (pinfunction "(T3/INT6)PE6_8") (pintype "bidirectional"))
    )
    (net (code "290") (name "unconnected-(IC3-(TOSC1)PG4-Pad29)") (class "Default")
      (node (ref "IC3") (pin "29") (pinfunction "(TOSC1)PG4_29") (pintype "bidirectional"))
    )
    (net (code "291") (name "unconnected-(IC3-(TOSC2)PG3-Pad28)") (class "Default")
      (node (ref "IC3") (pin "28") (pinfunction "(TOSC2)PG3_28") (pintype "bidirectional"))
    )
    (net (code "292") (name "unconnected-(IC3-(WR)PG0-Pad51)") (class "Default")
      (node (ref "IC3") (pin "51") (pinfunction "(WR)PG0_51") (pintype "bidirectional"))
    )
    (net (code "293") (name "unconnected-(IC3-(XCK0{slash}AIN0)PE2-Pad4)") (class "Default")
      (node (ref "IC3") (pin "4") (pinfunction "(XCK0/AIN0)PE2_4") (pintype "bidirectional"))
    )
    (net (code "294") (name "unconnected-(IC3-(XCK1)PD5-Pad48)") (class "Default")
      (node (ref "IC3") (pin "48") (pinfunction "(XCK1)PD5_48") (pintype "bidirectional"))
    )
    (net (code "295") (name "unconnected-(IC3-PH0(RXD2)-Pad12)") (class "Default")
      (node (ref "IC3") (pin "12") (pinfunction "PH0(RXD2)_12") (pintype "bidirectional"))
    )
    (net (code "296") (name "unconnected-(IC3-PH1(TXD2)-Pad13)") (class "Default")
      (node (ref "IC3") (pin "13") (pinfunction "PH1(TXD2)_13") (pintype "bidirectional"))
    )
    (net (code "297") (name "unconnected-(IC3-PH2(XCK2)-Pad14)") (class "Default")
      (node (ref "IC3") (pin "14") (pinfunction "PH2(XCK2)_14") (pintype "bidirectional"))
    )
    (net (code "298") (name "unconnected-(IC3-PH7(T4)-Pad27)") (class "Default")
      (node (ref "IC3") (pin "27") (pinfunction "PH7(T4)_27") (pintype "bidirectional"))
    )
    (net (code "299") (name "unconnected-(IC3-PJ0(RXD3{slash}PCINT9)-Pad63)") (class "Default")
      (node (ref "IC3") (pin "63") (pinfunction "PJ0(RXD3/PCINT9)_63") (pintype "bidirectional"))
    )
    (net (code "300") (name "unconnected-(IC3-PJ1(TXD3{slash}PCINT10)-Pad64)") (class "Default")
      (node (ref "IC3") (pin "64") (pinfunction "PJ1(TXD3/PCINT10)_64") (pintype "bidirectional"))
    )
    (net (code "301") (name "unconnected-(IC3-PJ2(XCK3{slash}PCINT11)-Pad65)") (class "Default")
      (node (ref "IC3") (pin "65") (pinfunction "PJ2(XCK3/PCINT11)_65") (pintype "bidirectional"))
    )
    (net (code "302") (name "unconnected-(IC3-PJ3(PCINT12)-Pad66)") (class "Default")
      (node (ref "IC3") (pin "66") (pinfunction "PJ3(PCINT12)_66") (pintype "bidirectional"))
    )
    (net (code "303") (name "unconnected-(IC3-PJ4(PCINT13)-Pad67)") (class "Default")
      (node (ref "IC3") (pin "67") (pinfunction "PJ4(PCINT13)_67") (pintype "bidirectional"))
    )
    (net (code "304") (name "unconnected-(IC3-PJ5(PCINT14)-Pad68)") (class "Default")
      (node (ref "IC3") (pin "68") (pinfunction "PJ5(PCINT14)_68") (pintype "bidirectional"))
    )
    (net (code "305") (name "unconnected-(IC3-PJ6(PCINT15)-Pad69)") (class "Default")
      (node (ref "IC3") (pin "69") (pinfunction "PJ6(PCINT15)_69") (pintype "bidirectional"))
    )
    (net (code "306") (name "unconnected-(IC3-PJ7-Pad79)") (class "Default")
      (node (ref "IC3") (pin "79") (pinfunction "PJ7_79") (pintype "bidirectional"))
    )
    (net (code "307") (name "unconnected-(IC3-PK0(ADC8{slash}PCINT16)-Pad89)") (class "Default")
      (node (ref "IC3") (pin "89") (pinfunction "PK0(ADC8/PCINT16)_89") (pintype "bidirectional"))
    )
    (net (code "308") (name "unconnected-(IC3-PK1(ADC9{slash}PCINT17)-Pad88)") (class "Default")
      (node (ref "IC3") (pin "88") (pinfunction "PK1(ADC9/PCINT17)_88") (pintype "bidirectional"))
    )
    (net (code "309") (name "unconnected-(IC3-PK2(ADC10{slash}PCINT18)-Pad87)") (class "Default")
      (node (ref "IC3") (pin "87") (pinfunction "PK2(ADC10/PCINT18)_87") (pintype "bidirectional"))
    )
    (net (code "310") (name "unconnected-(IC3-PK3(ADC11{slash}PCINT19)-Pad86)") (class "Default")
      (node (ref "IC3") (pin "86") (pinfunction "PK3(ADC11/PCINT19)_86") (pintype "bidirectional"))
    )
    (net (code "311") (name "unconnected-(IC3-PK4(ADC12{slash}PCINT20)-Pad85)") (class "Default")
      (node (ref "IC3") (pin "85") (pinfunction "PK4(ADC12/PCINT20)_85") (pintype "bidirectional"))
    )
    (net (code "312") (name "unconnected-(IC3-PK5(ADC13{slash}PCINT21)-Pad84)") (class "Default")
      (node (ref "IC3") (pin "84") (pinfunction "PK5(ADC13/PCINT21)_84") (pintype "bidirectional"))
    )
    (net (code "313") (name "unconnected-(IC3-PK6(ADC14{slash}PCINT22)-Pad83)") (class "Default")
      (node (ref "IC3") (pin "83") (pinfunction "PK6(ADC14/PCINT22)_83") (pintype "bidirectional"))
    )
    (net (code "314") (name "unconnected-(IC3-PK7(ADC15{slash}PCINT23)-Pad82)") (class "Default")
      (node (ref "IC3") (pin "82") (pinfunction "PK7(ADC15/PCINT23)_82") (pintype "bidirectional"))
    )
    (net (code "315") (name "unconnected-(IC3-PL0(ICP4)-Pad35)") (class "Default")
      (node (ref "IC3") (pin "35") (pinfunction "PL0(ICP4)_35") (pintype "bidirectional"))
    )
    (net (code "316") (name "unconnected-(IC3-PL1(ICP5)-Pad36)") (class "Default")
      (node (ref "IC3") (pin "36") (pinfunction "PL1(ICP5)_36") (pintype "bidirectional"))
    )
    (net (code "317") (name "unconnected-(IC3-PL2(T5)-Pad37)") (class "Default")
      (node (ref "IC3") (pin "37") (pinfunction "PL2(T5)_37") (pintype "bidirectional"))
    )
    (net (code "318") (name "unconnected-(IC3-PL3(OC5A)-Pad38)") (class "Default")
      (node (ref "IC3") (pin "38") (pinfunction "PL3(OC5A)_38") (pintype "bidirectional"))
    )
    (net (code "319") (name "unconnected-(IC3-PL4(OC5B)-Pad39)") (class "Default")
      (node (ref "IC3") (pin "39") (pinfunction "PL4(OC5B)_39") (pintype "bidirectional"))
    )
    (net (code "320") (name "unconnected-(IC3-PL5(OC5C)-Pad40)") (class "Default")
      (node (ref "IC3") (pin "40") (pinfunction "PL5(OC5C)_40") (pintype "bidirectional"))
    )
    (net (code "321") (name "unconnected-(IC3-PL6-Pad41)") (class "Default")
      (node (ref "IC3") (pin "41") (pinfunction "PL6_41") (pintype "bidirectional"))
    )
    (net (code "322") (name "unconnected-(IC3-PL7-Pad42)") (class "Default")
      (node (ref "IC3") (pin "42") (pinfunction "PL7_42") (pintype "bidirectional"))
    )
    (net (code "323") (name "unconnected-(JP1-Pad13)") (class "Default")
      (node (ref "JP1") (pin "13") (pinfunction "13_13") (pintype "passive"))
    )
    (net (code "324") (name "unconnected-(JP1-Pad14)") (class "Default")
      (node (ref "JP1") (pin "14") (pinfunction "14_14") (pintype "passive"))
    )
    (net (code "325") (name "unconnected-(JP1-Pad15)") (class "Default")
      (node (ref "JP1") (pin "15") (pinfunction "15_15") (pintype "passive"))
    )
    (net (code "326") (name "unconnected-(JP1-Pad18)") (class "Default")
      (node (ref "JP1") (pin "18") (pinfunction "18_18") (pintype "passive"))
    )
    (net (code "327") (name "unconnected-(JP1-Pad20)") (class "Default")
      (node (ref "JP1") (pin "20") (pinfunction "20_20") (pintype "passive"))
    )
    (net (code "328") (name "unconnected-(JP1-Pad21)") (class "Default")
      (node (ref "JP1") (pin "21") (pinfunction "21_21") (pintype "passive"))
    )
    (net (code "329") (name "unconnected-(JP1-Pad22)") (class "Default")
      (node (ref "JP1") (pin "22") (pinfunction "22_22") (pintype "passive"))
    )
    (net (code "330") (name "unconnected-(JP1-Pad24)") (class "Default")
      (node (ref "JP1") (pin "24") (pinfunction "24_24") (pintype "passive"))
    )
    (net (code "331") (name "unconnected-(JP1-Pad26)") (class "Default")
      (node (ref "JP1") (pin "26") (pinfunction "26_26") (pintype "passive"))
    )
  )
)
